# beltpack_v1_fixed.net
KiCad netlist of a schematic drawn in EAGLE
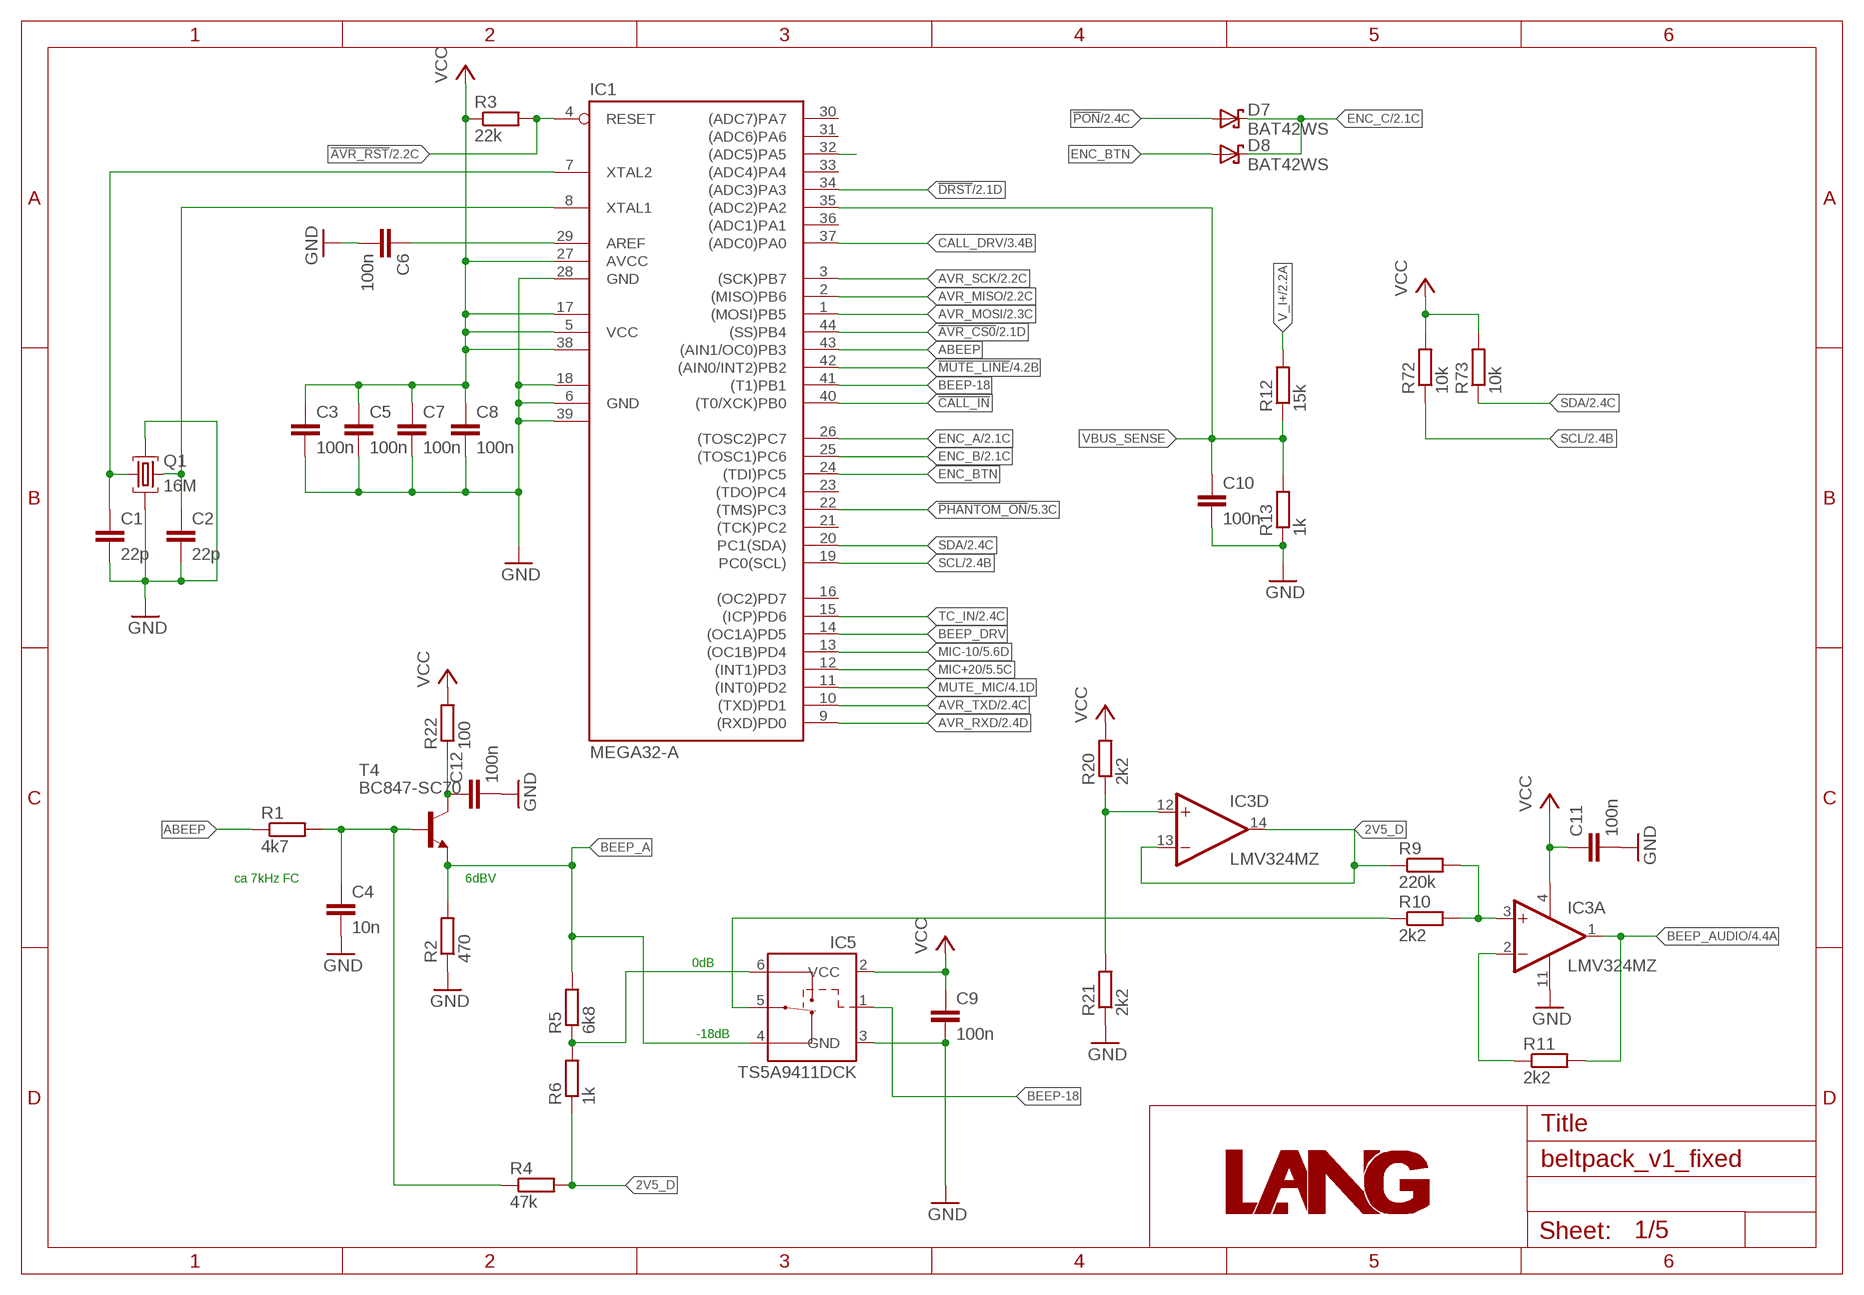
[diagram p0: schematic, sheet 1]
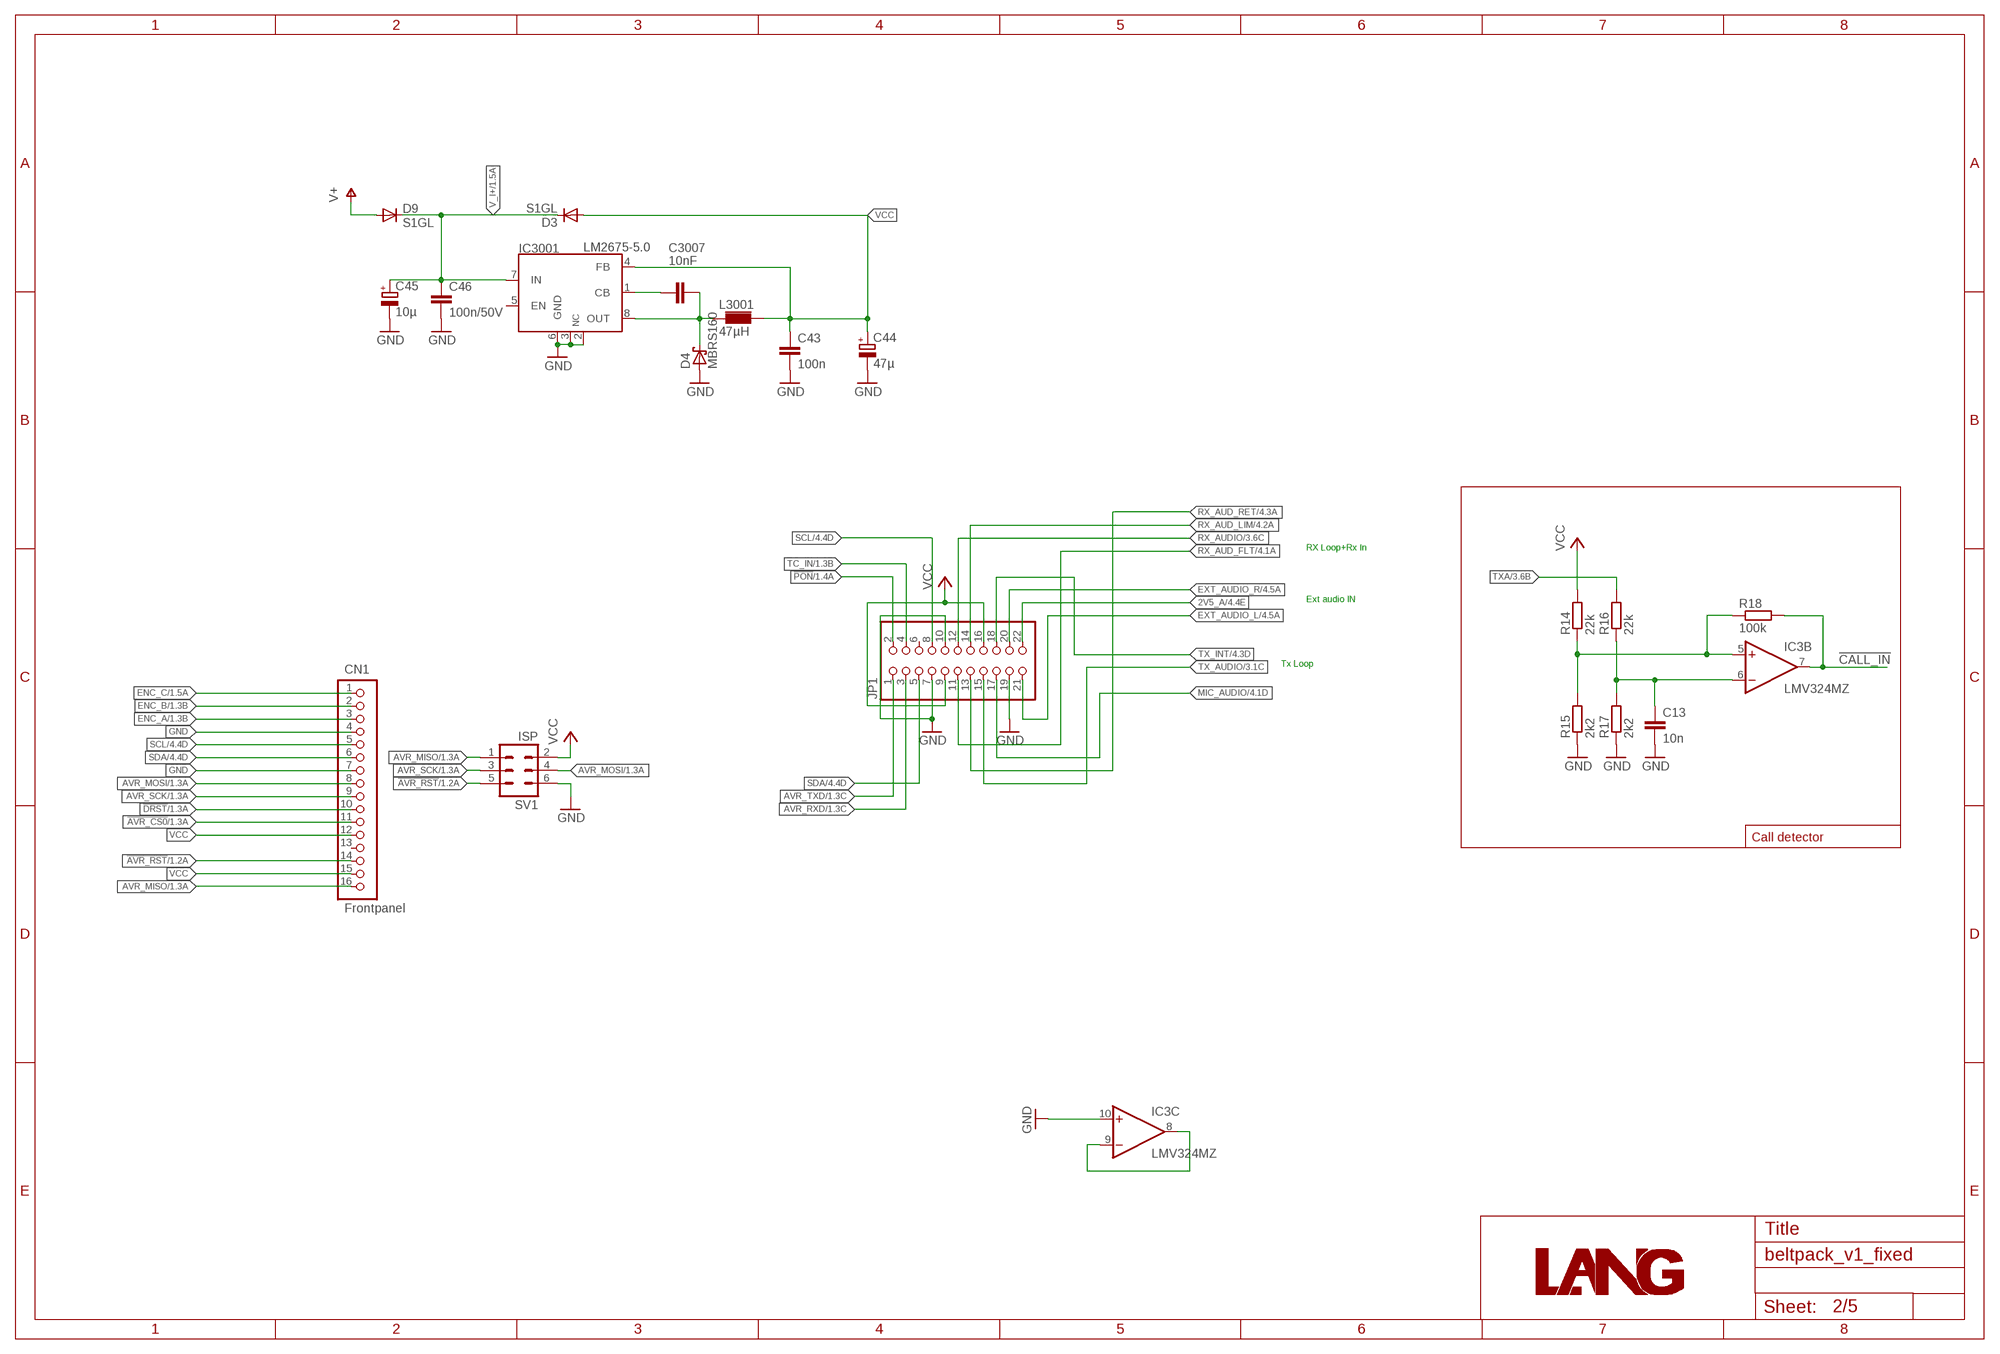
[diagram p1: schematic, sheet 2]
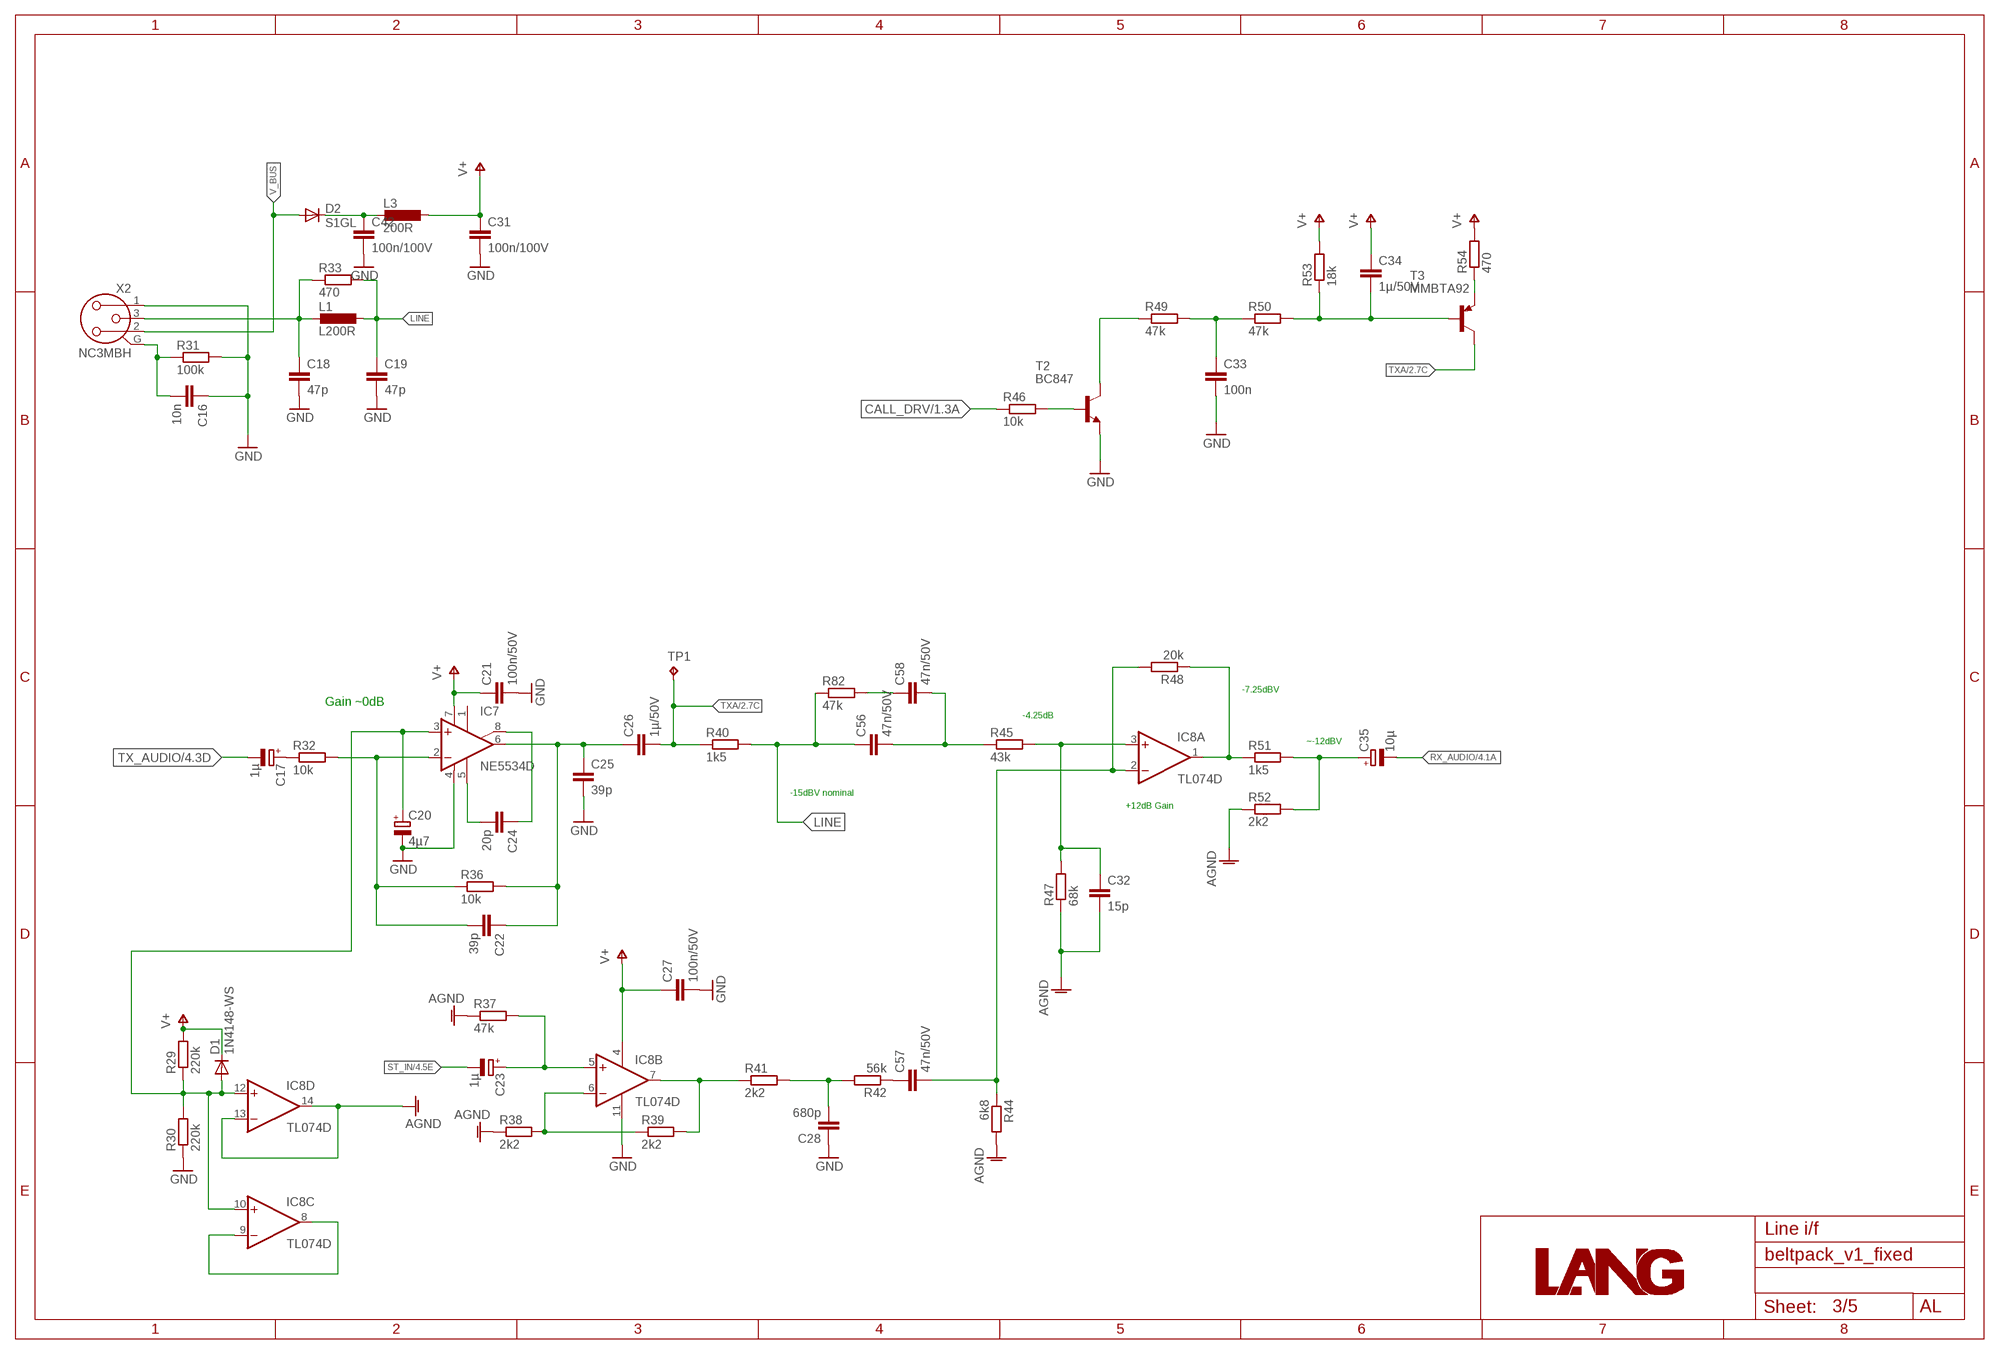
[diagram p2: schematic, sheet 3]
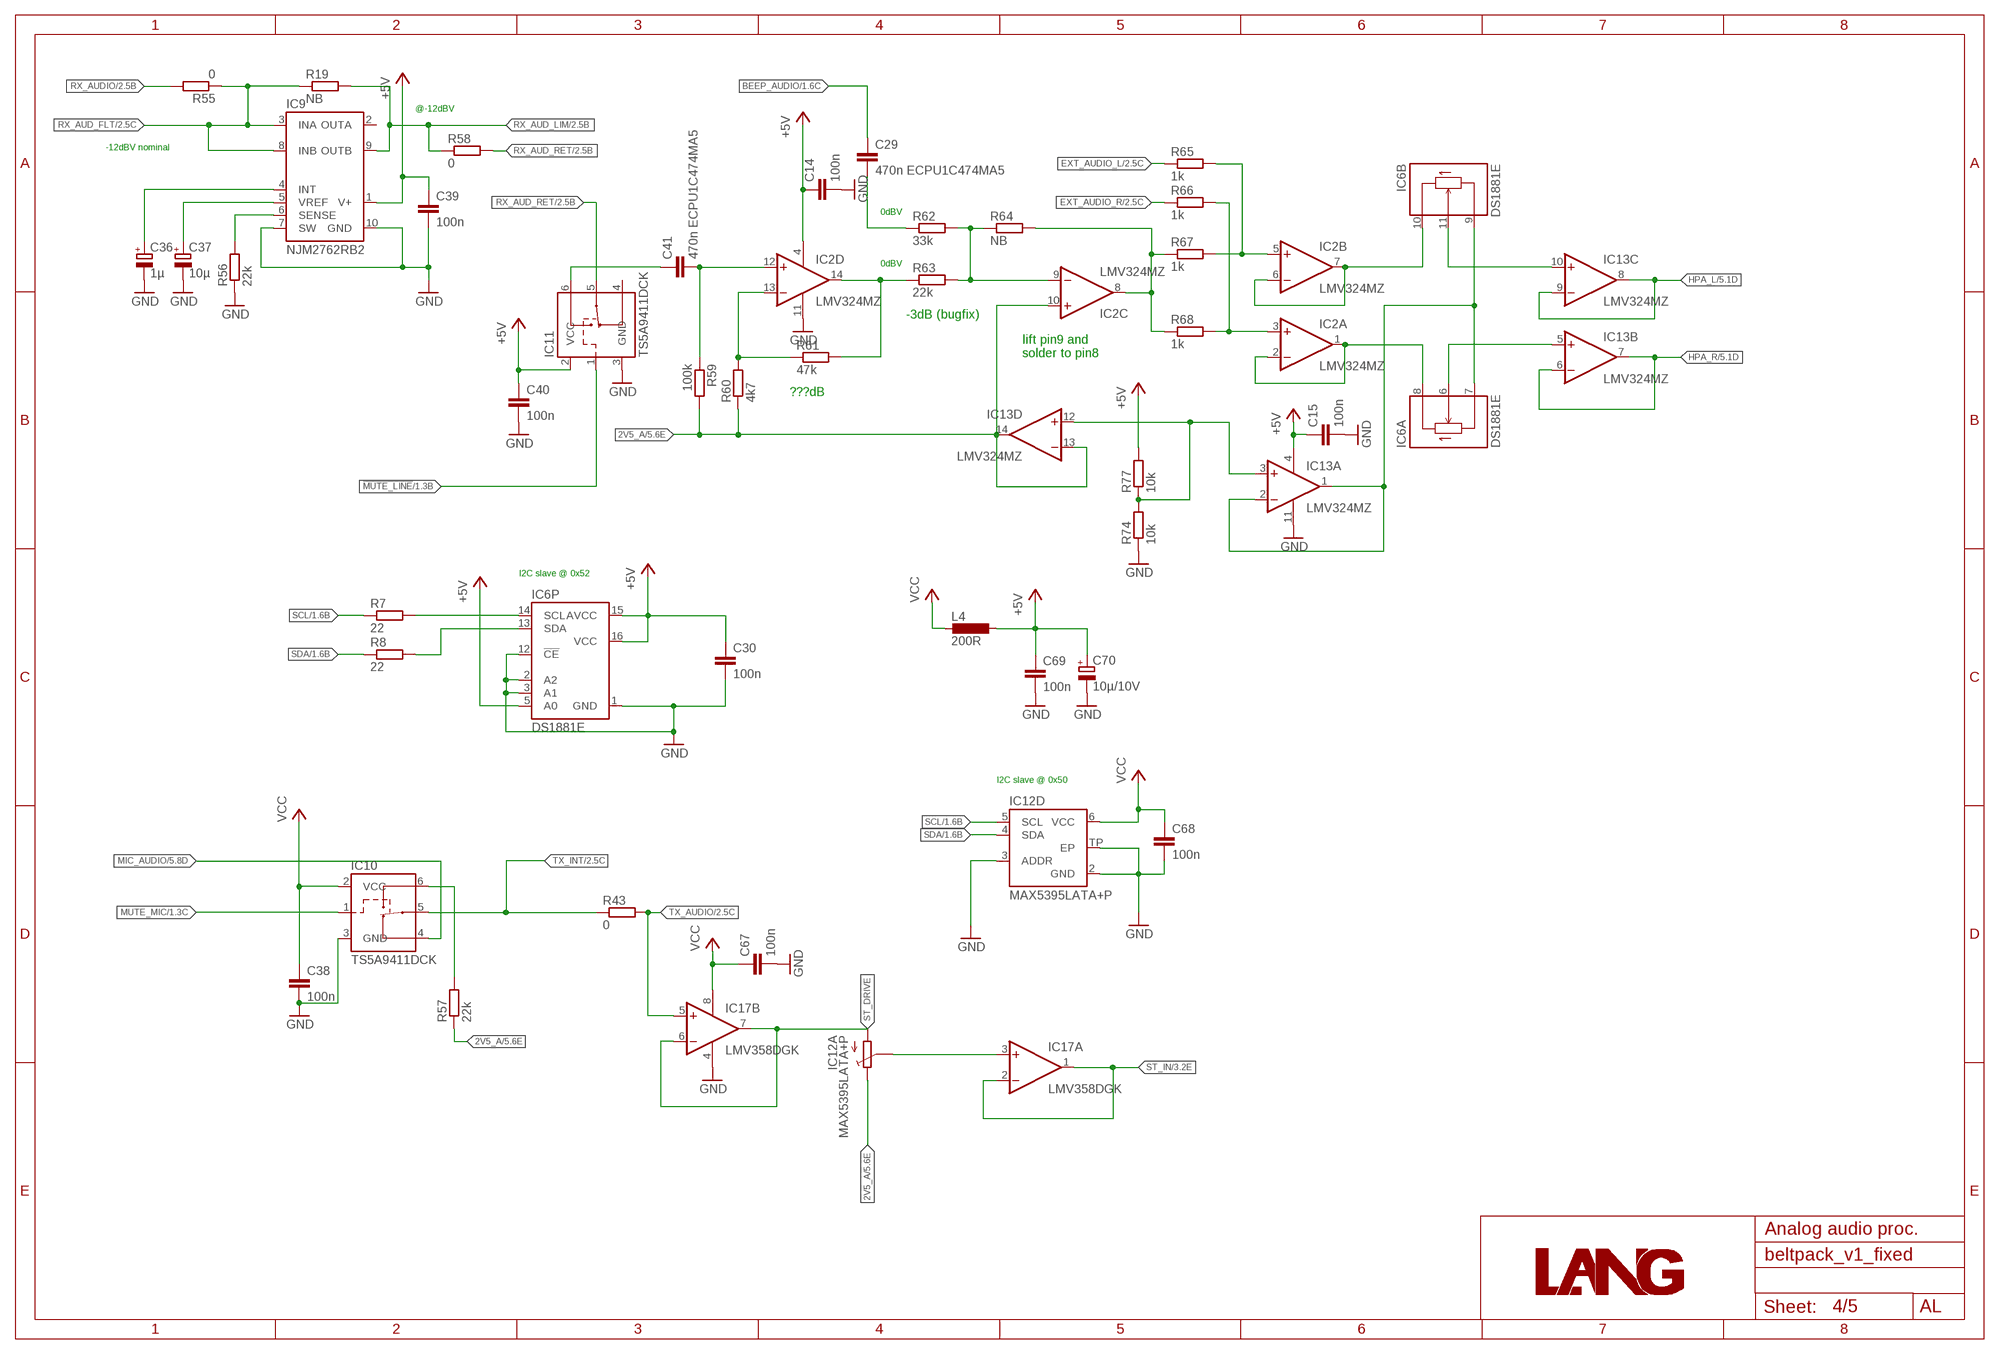
[diagram p3: schematic, sheet 4]
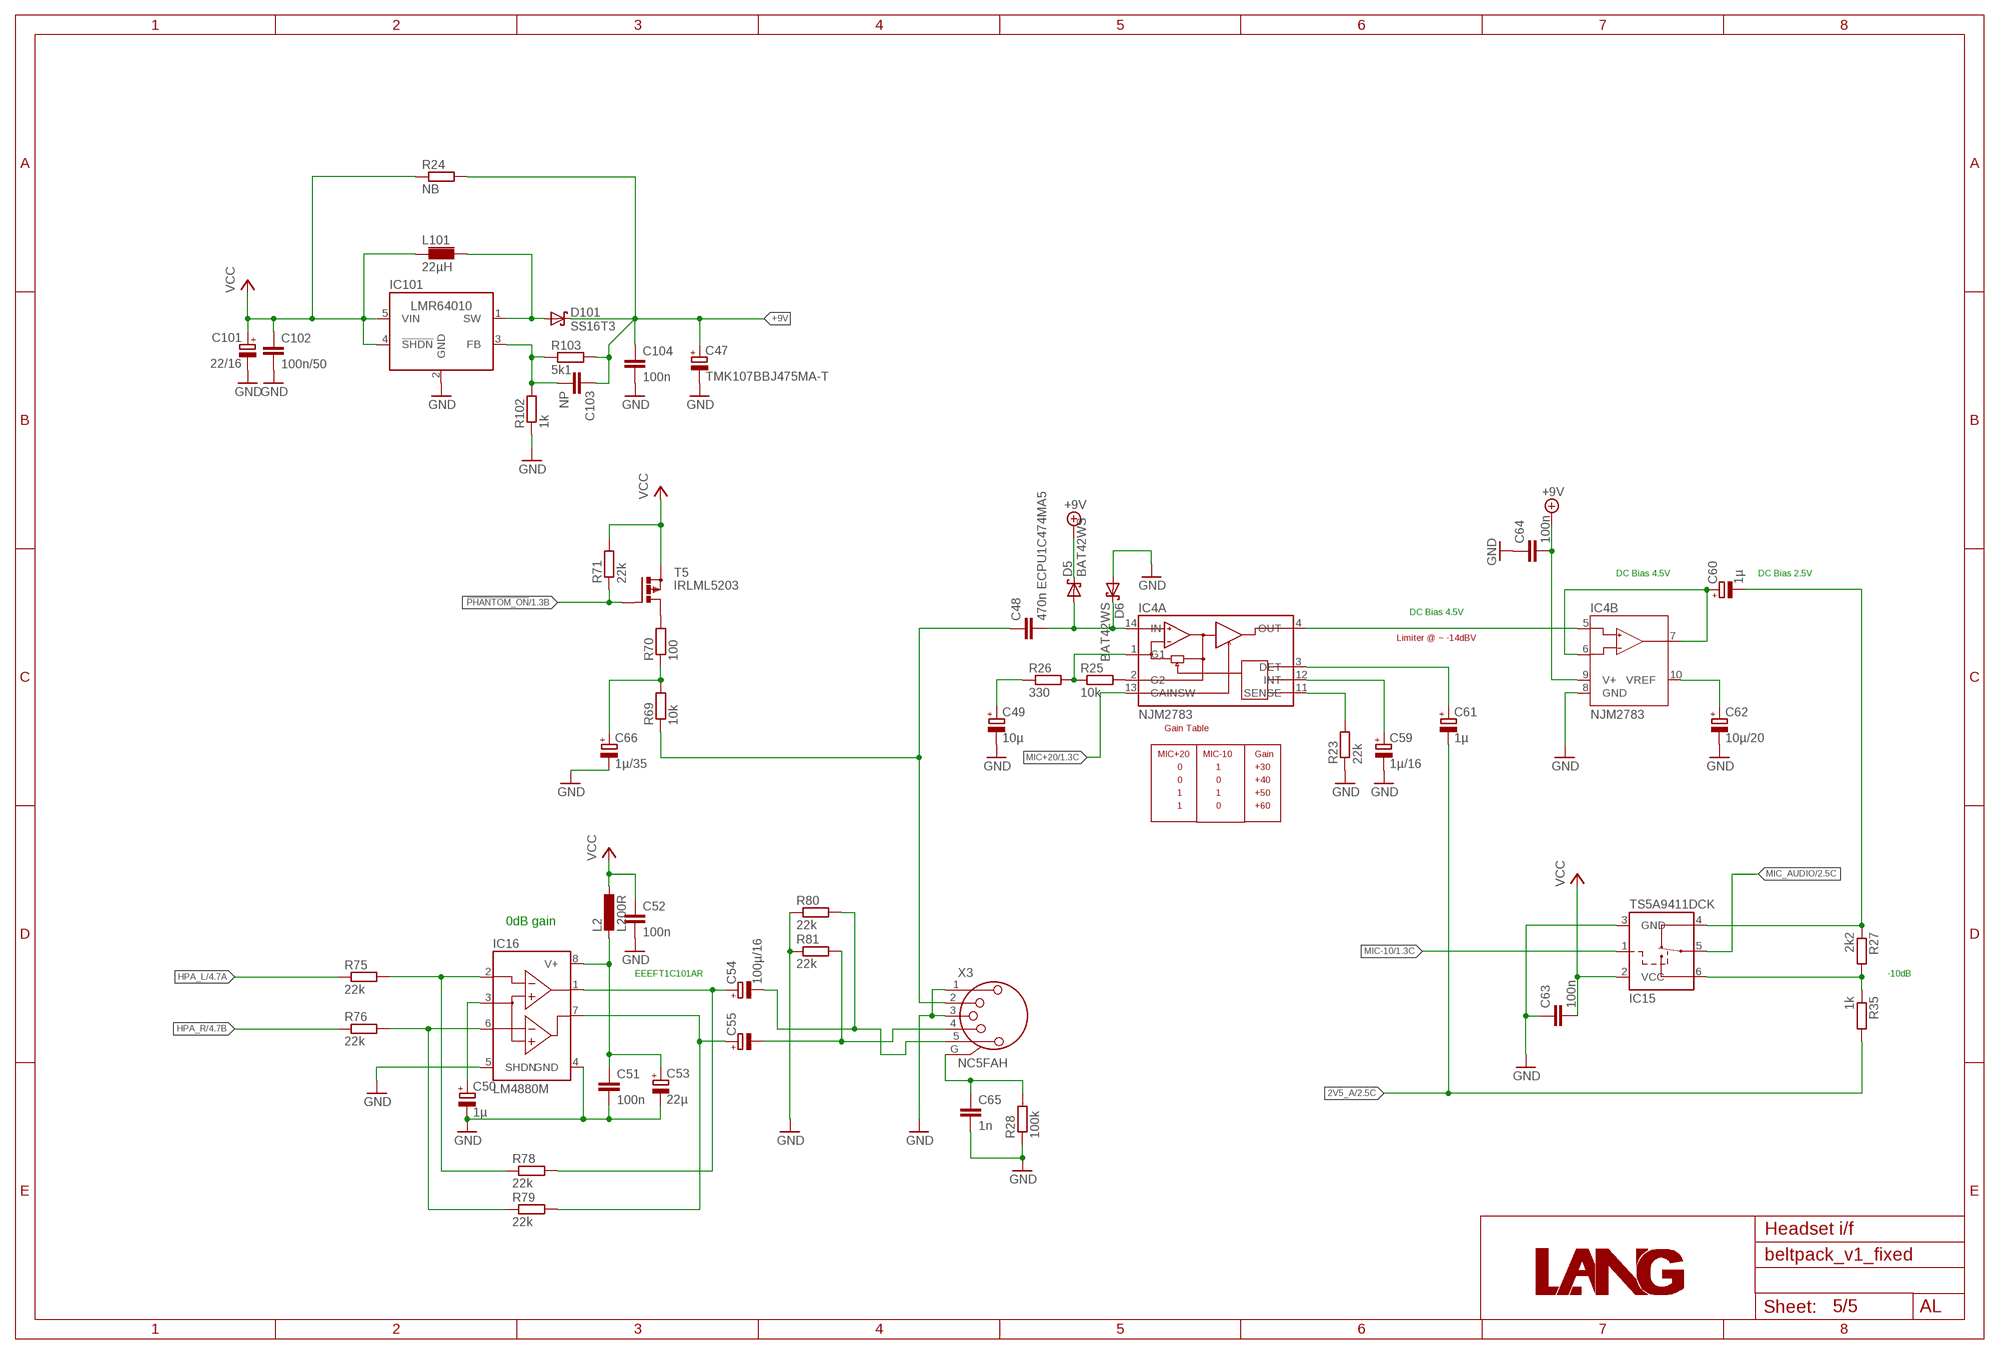
[diagram p4: schematic, sheet 5]

(export (version "E")
  (design (tool "Eeschema 10.0.6"))
  (components
    (comp (ref "C1")
      (value "22p")
      (footprint "eagle-import:C0603")
      (libsource (lib "eagle-import") (part "C-EUC0603"))
    )
    (comp (ref "C2")
      (value "22p")
      (footprint "eagle-import:C0603")
      (libsource (lib "eagle-import") (part "C-EUC0603"))
    )
    (comp (ref "C3")
      (value "100n")
      (footprint "eagle-import:C0603")
      (libsource (lib "eagle-import") (part "C-EUC0603"))
    )
    (comp (ref "C4")
      (value "10n")
      (footprint "eagle-import:C0603")
      (libsource (lib "eagle-import") (part "C-EUC0603"))
    )
    (comp (ref "C5")
      (value "100n")
      (footprint "eagle-import:C0603")
      (libsource (lib "eagle-import") (part "C-EUC0603"))
    )
    (comp (ref "C6")
      (value "100n")
      (footprint "eagle-import:C0603")
      (libsource (lib "eagle-import") (part "C-EUC0603"))
    )
    (comp (ref "C7")
      (value "100n")
      (footprint "eagle-import:C0603")
      (libsource (lib "eagle-import") (part "C-EUC0603"))
    )
    (comp (ref "C8")
      (value "100n")
      (footprint "eagle-import:C0603")
      (libsource (lib "eagle-import") (part "C-EUC0603"))
    )
    (comp (ref "C9")
      (value "100n")
      (footprint "eagle-import:C0603")
      (libsource (lib "eagle-import") (part "C-EUC0603"))
    )
    (comp (ref "C10")
      (value "100n")
      (footprint "eagle-import:C0603")
      (libsource (lib "eagle-import") (part "C-EUC0603"))
    )
    (comp (ref "C11")
      (value "100n")
      (footprint "eagle-import:C0603")
      (libsource (lib "eagle-import") (part "C-EUC0603"))
    )
    (comp (ref "C12")
      (value "100n")
      (footprint "eagle-import:C0603")
      (libsource (lib "eagle-import") (part "C-EUC0603"))
    )
    (comp (ref "D7")
      (value "BAT42WS")
      (footprint "eagle-import:SOD323R_INFINEON")
      (libsource (lib "eagle-import") (part "BAT4WS2"))
    )
    (comp (ref "D8")
      (value "BAT42WS")
      (footprint "eagle-import:SOD323R_INFINEON")
      (libsource (lib "eagle-import") (part "BAT4WS2"))
    )
    (comp (ref "IC1")
      (value "MEGA32-A")
      (footprint "eagle-import:TQFP44")
      (libsource (lib "eagle-import") (part "MEGA32-A"))
    )
    (comp (ref "IC3")
      (value "LMV324MZ")
      (footprint "eagle-import:TSSOP14")
      (libsource (lib "eagle-import") (part "LMV324?MZ"))
    )
    (comp (ref "IC5")
      (value "TS5A9411DCK")
      (footprint "eagle-import:SC70-6L")
      (libsource (lib "eagle-import") (part "TS5A9411DCK"))
    )
    (comp (ref "Q1")
      (value "16M")
      (footprint "eagle-import:MT")
      (libsource (lib "eagle-import") (part "CRYSTAL_SHIELDEDMT"))
    )
    (comp (ref "R1")
      (value "4k7")
      (footprint "eagle-import:R0603")
      (libsource (lib "eagle-import") (part "R-EU_R0603"))
    )
    (comp (ref "R2")
      (value "470")
      (footprint "eagle-import:R0603")
      (libsource (lib "eagle-import") (part "R-EU_R0603"))
    )
    (comp (ref "R3")
      (value "22k")
      (footprint "eagle-import:R0603")
      (libsource (lib "eagle-import") (part "R-EU_R0603"))
    )
    (comp (ref "R4")
      (value "47k")
      (footprint "eagle-import:R0603")
      (libsource (lib "eagle-import") (part "R-EU_R0603"))
    )
    (comp (ref "R5")
      (value "6k8")
      (footprint "eagle-import:R0603")
      (libsource (lib "eagle-import") (part "R-EU_R0603"))
    )
    (comp (ref "R6")
      (value "1k")
      (footprint "eagle-import:R0603")
      (libsource (lib "eagle-import") (part "R-EU_R0603"))
    )
    (comp (ref "R9")
      (value "220k")
      (footprint "eagle-import:R0603")
      (libsource (lib "eagle-import") (part "R-EU_R0603"))
    )
    (comp (ref "R10")
      (value "2k2")
      (footprint "eagle-import:R0603")
      (libsource (lib "eagle-import") (part "R-EU_R0603"))
    )
    (comp (ref "R11")
      (value "2k2")
      (footprint "eagle-import:R0603")
      (libsource (lib "eagle-import") (part "R-EU_R0603"))
    )
    (comp (ref "R12")
      (value "15k")
      (footprint "eagle-import:R0603")
      (libsource (lib "eagle-import") (part "R-EU_R0603"))
    )
    (comp (ref "R13")
      (value "1k")
      (footprint "eagle-import:R0603")
      (libsource (lib "eagle-import") (part "R-EU_R0603"))
    )
    (comp (ref "R20")
      (value "2k2")
      (footprint "eagle-import:R0603")
      (libsource (lib "eagle-import") (part "R-EU_R0603"))
    )
    (comp (ref "R21")
      (value "2k2")
      (footprint "eagle-import:R0603")
      (libsource (lib "eagle-import") (part "R-EU_R0603"))
    )
    (comp (ref "R22")
      (value "100")
      (footprint "eagle-import:R0603")
      (libsource (lib "eagle-import") (part "R-EU_R0603"))
    )
    (comp (ref "R72")
      (value "10k")
      (footprint "eagle-import:R0603")
      (libsource (lib "eagle-import") (part "R-EU_R0603"))
    )
    (comp (ref "R73")
      (value "10k")
      (footprint "eagle-import:R0603")
      (libsource (lib "eagle-import") (part "R-EU_R0603"))
    )
    (comp (ref "T4")
      (value "BC847-SC70")
      (footprint "eagle-import:SC70")
      (libsource (lib "eagle-import") (part "BC847-SC70"))
    )
    (comp (ref "C13")
      (value "10n")
      (footprint "eagle-import:C0603")
      (libsource (lib "eagle-import") (part "C-EUC0603"))
    )
    (comp (ref "C43")
      (value "100n")
      (footprint "eagle-import:C0603")
      (libsource (lib "eagle-import") (part "C-EUC0603"))
    )
    (comp (ref "C44")
      (value "47µ")
      (footprint "eagle-import:PANASONIC_B")
      (libsource (lib "eagle-import") (part "CPOL-EUB"))
    )
    (comp (ref "C45")
      (value "10µ")
      (footprint "eagle-import:PANASONIC_C")
      (libsource (lib "eagle-import") (part "CPOL-EUC"))
    )
    (comp (ref "C46")
      (value "100n/50V")
      (footprint "eagle-import:C0805")
      (libsource (lib "eagle-import") (part "C-EUC0805"))
    )
    (comp (ref "C3007")
      (value "10nF")
      (footprint "eagle-import:C0805")
      (libsource (lib "eagle-import") (part "C-EUC0805"))
    )
    (comp (ref "CN1")
      (value "Frontpanel")
      (footprint "eagle-import:MOLEX-505278-1633")
      (libsource (lib "eagle-import") (part "MOLEX-505278-1633"))
    )
    (comp (ref "D3")
      (value "S1GL")
      (footprint "eagle-import:DO219AB")
      (libsource (lib "eagle-import") (part "DIODE-DO219AB"))
    )
    (comp (ref "D4")
      (value "MBRS160")
      (footprint "eagle-import:SMB")
      (libsource (lib "eagle-import") (part "SCHOTTKY-DIODESMD"))
    )
    (comp (ref "D9")
      (value "S1GL")
      (footprint "eagle-import:DO219AB")
      (libsource (lib "eagle-import") (part "DIODE-DO219AB"))
    )
    (comp (ref "IC3001")
      (value "LM2675-5.0")
      (footprint "eagle-import:SO-08")
      (libsource (lib "eagle-import") (part "LM2676_SOIC"))
    )
    (comp (ref "JP1")
      (value "PINHD-2X11")
      (footprint "eagle-import:2X11")
      (libsource (lib "eagle-import") (part "PINHD-2X11"))
    )
    (comp (ref "L3001")
      (value "47µH")
      (footprint "eagle-import:PISM")
      (libsource (lib "eagle-import") (part "L-PISM"))
    )
    (comp (ref "R14")
      (value "22k")
      (footprint "eagle-import:R0603")
      (libsource (lib "eagle-import") (part "R-EU_R0603"))
    )
    (comp (ref "R15")
      (value "2k2")
      (footprint "eagle-import:R0603")
      (libsource (lib "eagle-import") (part "R-EU_R0603"))
    )
    (comp (ref "R16")
      (value "22k")
      (footprint "eagle-import:R0603")
      (libsource (lib "eagle-import") (part "R-EU_R0603"))
    )
    (comp (ref "R17")
      (value "2k2")
      (footprint "eagle-import:R0603")
      (libsource (lib "eagle-import") (part "R-EU_R0603"))
    )
    (comp (ref "R18")
      (value "100k")
      (footprint "eagle-import:R0603")
      (libsource (lib "eagle-import") (part "R-EU_R0603"))
    )
    (comp (ref "SV1")
      (value "ISP")
      (footprint "eagle-import:ML6")
      (libsource (lib "eagle-import") (part "ML6"))
    )
    (comp (ref "C14")
      (value "100n")
      (footprint "eagle-import:C0603")
      (libsource (lib "eagle-import") (part "C-EUC0603"))
    )
    (comp (ref "C15")
      (value "100n")
      (footprint "eagle-import:C0603")
      (libsource (lib "eagle-import") (part "C-EUC0603"))
    )
    (comp (ref "C29")
      (value "470n ECPU1C474MA5")
      (footprint "eagle-import:C_PANASONIC_H3")
      (libsource (lib "eagle-import") (part "C-EUPAN_H3"))
    )
    (comp (ref "C30")
      (value "100n")
      (footprint "eagle-import:C0603")
      (libsource (lib "eagle-import") (part "C-EUC0603"))
    )
    (comp (ref "C36")
      (value "1µ")
      (footprint "eagle-import:PANASONIC_B")
      (libsource (lib "eagle-import") (part "CPOL-EUB"))
    )
    (comp (ref "C37")
      (value "10µ")
      (footprint "eagle-import:PANASONIC_B")
      (libsource (lib "eagle-import") (part "CPOL-EUB"))
    )
    (comp (ref "C38")
      (value "100n")
      (footprint "eagle-import:C0402")
      (libsource (lib "eagle-import") (part "C-EUC0402"))
    )
    (comp (ref "C39")
      (value "100n")
      (footprint "eagle-import:C0603")
      (libsource (lib "eagle-import") (part "C-EUC0603"))
    )
    (comp (ref "C40")
      (value "100n")
      (footprint "eagle-import:C0603")
      (libsource (lib "eagle-import") (part "C-EUC0603"))
    )
    (comp (ref "C41")
      (value "470n ECPU1C474MA5")
      (footprint "eagle-import:C_PANASONIC_H3")
      (libsource (lib "eagle-import") (part "C-EUPAN_H3"))
    )
    (comp (ref "C67")
      (value "100n")
      (footprint "eagle-import:C0603")
      (libsource (lib "eagle-import") (part "C-EUC0603"))
    )
    (comp (ref "C68")
      (value "100n")
      (footprint "eagle-import:C0603")
      (libsource (lib "eagle-import") (part "C-EUC0603"))
    )
    (comp (ref "C69")
      (value "100n")
      (footprint "eagle-import:C0603")
      (libsource (lib "eagle-import") (part "C-EUC0603"))
    )
    (comp (ref "C70")
      (value "10µ/10V")
      (footprint "eagle-import:A_3216-18R")
      (libsource (lib "eagle-import") (part "CPOL-EUA/3216-18R"))
    )
    (comp (ref "IC2")
      (value "LMV324MZ")
      (footprint "eagle-import:TSSOP14")
      (libsource (lib "eagle-import") (part "LMV324?MZ"))
    )
    (comp (ref "IC6")
      (value "DS1881E")
      (footprint "eagle-import:TSSOP16")
      (libsource (lib "eagle-import") (part "DS1881E"))
    )
    (comp (ref "IC9")
      (value "NJM2762RB2")
      (footprint "eagle-import:MSOP10")
      (libsource (lib "eagle-import") (part "NJM2762RB2"))
    )
    (comp (ref "IC10")
      (value "TS5A9411DCK")
      (footprint "eagle-import:SC70-6L")
      (libsource (lib "eagle-import") (part "TS5A9411DCK"))
    )
    (comp (ref "IC11")
      (value "TS5A9411DCK")
      (footprint "eagle-import:SC70-6L")
      (libsource (lib "eagle-import") (part "TS5A9411DCK"))
    )
    (comp (ref "IC12")
      (value "MAX5395LATA+P")
      (footprint "eagle-import:8TDFN-EP")
      (libsource (lib "eagle-import") (part "MAX5395ATA+PL"))
    )
    (comp (ref "IC13")
      (value "LMV324MZ")
      (footprint "eagle-import:TSSOP14")
      (libsource (lib "eagle-import") (part "LMV324?MZ"))
    )
    (comp (ref "IC17")
      (value "LMV358DGK")
      (footprint "eagle-import:VSOP8")
      (libsource (lib "eagle-import") (part "LMV358?DGK"))
    )
    (comp (ref "L4")
      (value "200R")
      (footprint "eagle-import:R0805")
      (libsource (lib "eagle-import") (part "L-EU_L0805"))
    )
    (comp (ref "R7")
      (value "22")
      (footprint "eagle-import:R0402")
      (libsource (lib "eagle-import") (part "R-EU_R0402"))
    )
    (comp (ref "R8")
      (value "22")
      (footprint "eagle-import:R0402")
      (libsource (lib "eagle-import") (part "R-EU_R0402"))
    )
    (comp (ref "R19")
      (value "NB")
      (footprint "eagle-import:R0603")
      (libsource (lib "eagle-import") (part "R-EU_R0603"))
    )
    (comp (ref "R43")
      (value "0")
      (footprint "eagle-import:R0603")
      (libsource (lib "eagle-import") (part "R-EU_R0603"))
    )
    (comp (ref "R55")
      (value "0")
      (footprint "eagle-import:R0603")
      (libsource (lib "eagle-import") (part "R-EU_R0603"))
    )
    (comp (ref "R56")
      (value "22k")
      (footprint "eagle-import:R0603")
      (libsource (lib "eagle-import") (part "R-EU_R0603"))
    )
    (comp (ref "R57")
      (value "22k")
      (footprint "eagle-import:R0603")
      (libsource (lib "eagle-import") (part "R-EU_R0603"))
    )
    (comp (ref "R58")
      (value "0")
      (footprint "eagle-import:R0603")
      (libsource (lib "eagle-import") (part "R-EU_R0603"))
    )
    (comp (ref "R59")
      (value "100k")
      (footprint "eagle-import:R0603")
      (libsource (lib "eagle-import") (part "R-EU_R0603"))
    )
    (comp (ref "R60")
      (value "4k7")
      (footprint "eagle-import:R0603")
      (libsource (lib "eagle-import") (part "R-EU_R0603"))
    )
    (comp (ref "R61")
      (value "47k")
      (footprint "eagle-import:R0603")
      (libsource (lib "eagle-import") (part "R-EU_R0603"))
    )
    (comp (ref "R62")
      (value "33k")
      (footprint "eagle-import:R0603")
      (libsource (lib "eagle-import") (part "R-EU_R0603"))
    )
    (comp (ref "R63")
      (value "22k")
      (footprint "eagle-import:R0603")
      (libsource (lib "eagle-import") (part "R-EU_R0603"))
    )
    (comp (ref "R64")
      (value "NB")
      (footprint "eagle-import:R0603")
      (libsource (lib "eagle-import") (part "R-EU_R0603"))
    )
    (comp (ref "R65")
      (value "1k")
      (footprint "eagle-import:R0603")
      (libsource (lib "eagle-import") (part "R-EU_R0603"))
    )
    (comp (ref "R66")
      (value "1k")
      (footprint "eagle-import:R0603")
      (libsource (lib "eagle-import") (part "R-EU_R0603"))
    )
    (comp (ref "R67")
      (value "1k")
      (footprint "eagle-import:R0603")
      (libsource (lib "eagle-import") (part "R-EU_R0603"))
    )
    (comp (ref "R68")
      (value "1k")
      (footprint "eagle-import:R0603")
      (libsource (lib "eagle-import") (part "R-EU_R0603"))
    )
    (comp (ref "R74")
      (value "10k")
      (footprint "eagle-import:R0603")
      (libsource (lib "eagle-import") (part "R-EU_R0603"))
    )
    (comp (ref "R77")
      (value "10k")
      (footprint "eagle-import:R0603")
      (libsource (lib "eagle-import") (part "R-EU_R0603"))
    )
    (comp (ref "C47")
      (value "TMK107BBJ475MA-T")
      (footprint "eagle-import:PANASONIC_B")
      (libsource (lib "eagle-import") (part "CPOL-EUB"))
    )
    (comp (ref "C48")
      (value "470n ECPU1C474MA5")
      (footprint "eagle-import:C_PANASONIC_H3")
      (libsource (lib "eagle-import") (part "C-EUPAN_H3"))
    )
    (comp (ref "C49")
      (value "10µ")
      (footprint "eagle-import:PANASONIC_B")
      (libsource (lib "eagle-import") (part "CPOL-EUB"))
    )
    (comp (ref "C50")
      (value "1µ")
      (footprint "eagle-import:PANASONIC_B")
      (libsource (lib "eagle-import") (part "CPOL-EUB"))
    )
    (comp (ref "C51")
      (value "100n")
      (footprint "eagle-import:C0603")
      (libsource (lib "eagle-import") (part "C-EUC0603"))
    )
    (comp (ref "C52")
      (value "100n")
      (footprint "eagle-import:C0603")
      (libsource (lib "eagle-import") (part "C-EUC0603"))
    )
    (comp (ref "C53")
      (value "22µ")
      (footprint "eagle-import:PANASONIC_C")
      (libsource (lib "eagle-import") (part "CPOL-EUC"))
    )
    (comp (ref "C54")
      (value "100µ/16")
      (footprint "eagle-import:PANASONIC_C")
      (libsource (lib "eagle-import") (part "CPOL-EUC"))
    )
    (comp (ref "C55")
      (value "100µ/16")
      (footprint "eagle-import:PANASONIC_C")
      (libsource (lib "eagle-import") (part "CPOL-EUC"))
    )
    (comp (ref "C59")
      (value "1µ/16")
      (footprint "eagle-import:A_3216-18R")
      (libsource (lib "eagle-import") (part "CPOL-EUA/3216-18R"))
    )
    (comp (ref "C60")
      (value "1µ")
      (footprint "eagle-import:PANASONIC_B")
      (libsource (lib "eagle-import") (part "CPOL-EUB"))
    )
    (comp (ref "C61")
      (value "1µ")
      (footprint "eagle-import:PANASONIC_B")
      (libsource (lib "eagle-import") (part "CPOL-EUB"))
    )
    (comp (ref "C62")
      (value "10µ/20")
      (footprint "eagle-import:B_3528-21R")
      (libsource (lib "eagle-import") (part "CPOL-EUB/3528-21R"))
    )
    (comp (ref "C63")
      (value "100n")
      (footprint "eagle-import:C0402")
      (libsource (lib "eagle-import") (part "C-EUC0402"))
    )
    (comp (ref "C64")
      (value "100n")
      (footprint "eagle-import:C0603")
      (libsource (lib "eagle-import") (part "C-EUC0603"))
    )
    (comp (ref "C65")
      (value "1n")
      (footprint "eagle-import:C0603")
      (libsource (lib "eagle-import") (part "C-EUC0603"))
    )
    (comp (ref "C66")
      (value "1µ/35")
      (footprint "eagle-import:B_3528-21R")
      (libsource (lib "eagle-import") (part "CPOL-EUB/3528-21R"))
    )
    (comp (ref "C101")
      (value "22/16")
      (footprint "eagle-import:B_3528-21R")
      (libsource (lib "eagle-import") (part "CPOL-EUB/3528-21R"))
    )
    (comp (ref "C102")
      (value "100n/50")
      (footprint "eagle-import:C0805")
      (libsource (lib "eagle-import") (part "C-EUC0805"))
    )
    (comp (ref "C103")
      (value "NP")
      (footprint "eagle-import:C0603")
      (libsource (lib "eagle-import") (part "C-EUC0603"))
    )
    (comp (ref "C104")
      (value "100n")
      (footprint "eagle-import:C0603")
      (libsource (lib "eagle-import") (part "C-EUC0603"))
    )
    (comp (ref "D5")
      (value "BAT42WS")
      (footprint "eagle-import:SOD323R_INFINEON")
      (libsource (lib "eagle-import") (part "BAT4WS2"))
    )
    (comp (ref "D6")
      (value "BAT42WS")
      (footprint "eagle-import:SOD323R_INFINEON")
      (libsource (lib "eagle-import") (part "BAT4WS2"))
    )
    (comp (ref "D101")
      (value "SS16T3")
      (footprint "eagle-import:SMA")
      (libsource (lib "eagle-import") (part "SS16T3"))
    )
    (comp (ref "IC4")
      (value "NJM2783")
      (footprint "eagle-import:TSSOP14")
      (libsource (lib "eagle-import") (part "NJM2783"))
    )
    (comp (ref "IC15")
      (value "TS5A9411DCK")
      (footprint "eagle-import:SC70-6L")
      (libsource (lib "eagle-import") (part "TS5A9411DCK"))
    )
    (comp (ref "IC16")
      (value "LM4880M")
      (footprint "eagle-import:SOIC8")
      (libsource (lib "eagle-import") (part "LM4880M"))
    )
    (comp (ref "IC101")
      (value "LMR64010")
      (footprint "eagle-import:SOT23-5")
      (libsource (lib "eagle-import") (part "LMR64010"))
    )
    (comp (ref "L2")
      (value "L200R")
      (footprint "eagle-import:R0805")
      (libsource (lib "eagle-import") (part "L-EU_L0805"))
    )
    (comp (ref "L101")
      (value "22µH")
      (footprint "eagle-import:PISG")
      (libsource (lib "eagle-import") (part "L-PISG"))
    )
    (comp (ref "R23")
      (value "22k")
      (footprint "eagle-import:R0603")
      (libsource (lib "eagle-import") (part "R-EU_R0603"))
    )
    (comp (ref "R24")
      (value "NB")
      (footprint "eagle-import:R0603")
      (libsource (lib "eagle-import") (part "R-EU_R0603"))
    )
    (comp (ref "R25")
      (value "10k")
      (footprint "eagle-import:R0603")
      (libsource (lib "eagle-import") (part "R-EU_R0603"))
    )
    (comp (ref "R26")
      (value "330")
      (footprint "eagle-import:R0603")
      (libsource (lib "eagle-import") (part "R-EU_R0603"))
    )
    (comp (ref "R27")
      (value "2k2")
      (footprint "eagle-import:R0603")
      (libsource (lib "eagle-import") (part "R-EU_R0603"))
    )
    (comp (ref "R28")
      (value "100k")
      (footprint "eagle-import:R0603")
      (libsource (lib "eagle-import") (part "R-EU_R0603"))
    )
    (comp (ref "R35")
      (value "1k")
      (footprint "eagle-import:R0603")
      (libsource (lib "eagle-import") (part "R-EU_R0603"))
    )
    (comp (ref "R69")
      (value "10k")
      (footprint "eagle-import:R0603")
      (libsource (lib "eagle-import") (part "R-EU_R0603"))
    )
    (comp (ref "R70")
      (value "100")
      (footprint "eagle-import:R0603")
      (libsource (lib "eagle-import") (part "R-EU_R0603"))
    )
    (comp (ref "R71")
      (value "22k")
      (footprint "eagle-import:R0603")
      (libsource (lib "eagle-import") (part "R-EU_R0603"))
    )
    (comp (ref "R75")
      (value "22k")
      (footprint "eagle-import:R0603")
      (libsource (lib "eagle-import") (part "R-EU_R0603"))
    )
    (comp (ref "R76")
      (value "22k")
      (footprint "eagle-import:R0603")
      (libsource (lib "eagle-import") (part "R-EU_R0603"))
    )
    (comp (ref "R78")
      (value "22k")
      (footprint "eagle-import:R0603")
      (libsource (lib "eagle-import") (part "R-EU_R0603"))
    )
    (comp (ref "R79")
      (value "22k")
      (footprint "eagle-import:R0603")
      (libsource (lib "eagle-import") (part "R-EU_R0603"))
    )
    (comp (ref "R80")
      (value "22k")
      (footprint "eagle-import:R0603")
      (libsource (lib "eagle-import") (part "R-EU_R0603"))
    )
    (comp (ref "R81")
      (value "22k")
      (footprint "eagle-import:R0603")
      (libsource (lib "eagle-import") (part "R-EU_R0603"))
    )
    (comp (ref "R102")
      (value "1k")
      (footprint "eagle-import:R0603")
      (libsource (lib "eagle-import") (part "R-EU_R0603"))
    )
    (comp (ref "R103")
      (value "5k1")
      (footprint "eagle-import:R0603")
      (libsource (lib "eagle-import") (part "R-EU_R0603"))
    )
    (comp (ref "T5")
      (value "IRLML5203")
      (footprint "eagle-import:SOT23")
      (libsource (lib "eagle-import") (part "IRLML5203"))
    )
    (comp (ref "X3")
      (value "NC5FAH")
      (footprint "eagle-import:NC5FAH")
      (libsource (lib "eagle-import") (part "NC5FAH"))
    )
    (comp (ref "C16")
      (value "10n")
      (footprint "eagle-import:C0805")
      (libsource (lib "eagle-import") (part "C-EUC0805"))
    )
    (comp (ref "C17")
      (value "1µ")
      (footprint "eagle-import:PANASONIC_B")
      (libsource (lib "eagle-import") (part "CPOL-EUB"))
    )
    (comp (ref "C18")
      (value "47p")
      (footprint "eagle-import:C0603")
      (libsource (lib "eagle-import") (part "C-EUC0603"))
    )
    (comp (ref "C19")
      (value "47p")
      (footprint "eagle-import:C0603")
      (libsource (lib "eagle-import") (part "C-EUC0603"))
    )
    (comp (ref "C20")
      (value "4µ7")
      (footprint "eagle-import:PANASONIC_B")
      (libsource (lib "eagle-import") (part "CPOL-EUB"))
    )
    (comp (ref "C21")
      (value "100n/50V")
      (footprint "eagle-import:C0805")
      (libsource (lib "eagle-import") (part "C-EUC0805"))
    )
    (comp (ref "C22")
      (value "39p")
      (footprint "eagle-import:C0603")
      (libsource (lib "eagle-import") (part "C-EUC0603"))
    )
    (comp (ref "C23")
      (value "1µ")
      (footprint "eagle-import:PANASONIC_B")
      (libsource (lib "eagle-import") (part "CPOL-EUB"))
    )
    (comp (ref "C24")
      (value "20p")
      (footprint "eagle-import:C0603")
      (libsource (lib "eagle-import") (part "C-EUC0603"))
    )
    (comp (ref "C25")
      (value "39p")
      (footprint "eagle-import:C0603")
      (libsource (lib "eagle-import") (part "C-EUC0603"))
    )
    (comp (ref "C26")
      (value "1µ/50V")
      (footprint "eagle-import:C1206")
      (libsource (lib "eagle-import") (part "C-EUC1206"))
    )
    (comp (ref "C27")
      (value "100n/50V")
      (footprint "eagle-import:C0805")
      (libsource (lib "eagle-import") (part "C-EUC0805"))
    )
    (comp (ref "C28")
      (value "680p")
      (footprint "eagle-import:C0603")
      (libsource (lib "eagle-import") (part "C-EUC0603"))
    )
    (comp (ref "C31")
      (value "100n/100V")
      (footprint "eagle-import:C1206")
      (libsource (lib "eagle-import") (part "C-EUC1206"))
    )
    (comp (ref "C32")
      (value "15p")
      (footprint "eagle-import:C0603")
      (libsource (lib "eagle-import") (part "C-EUC0603"))
    )
    (comp (ref "C33")
      (value "100n")
      (footprint "eagle-import:C0603")
      (libsource (lib "eagle-import") (part "C-EUC0603"))
    )
    (comp (ref "C34")
      (value "1µ/50V")
      (footprint "eagle-import:C1206")
      (libsource (lib "eagle-import") (part "C-EUC1206"))
    )
    (comp (ref "C35")
      (value "10µ")
      (footprint "eagle-import:PANASONIC_B")
      (libsource (lib "eagle-import") (part "CPOL-EUB"))
    )
    (comp (ref "C42")
      (value "100n/100V")
      (footprint "eagle-import:C1206")
      (libsource (lib "eagle-import") (part "C-EUC1206"))
    )
    (comp (ref "C56")
      (value "47n/50V")
      (footprint "eagle-import:C_PAN_ECHU_E1")
      (libsource (lib "eagle-import") (part "C-EUPAN_E1"))
    )
    (comp (ref "C57")
      (value "47n/50V")
      (footprint "eagle-import:C_PAN_ECHU_E1")
      (libsource (lib "eagle-import") (part "C-EUPAN_E1"))
    )
    (comp (ref "C58")
      (value "47n/50V")
      (footprint "eagle-import:C_PAN_ECHU_E1")
      (libsource (lib "eagle-import") (part "C-EUPAN_E1"))
    )
    (comp (ref "D1")
      (value "1N4148-WS")
      (footprint "eagle-import:SOD323")
      (libsource (lib "eagle-import") (part "1N4148-WS"))
    )
    (comp (ref "D2")
      (value "S1GL")
      (footprint "eagle-import:DO219AB")
      (libsource (lib "eagle-import") (part "DIODE-DO219AB"))
    )
    (comp (ref "IC7")
      (value "NE5534D")
      (footprint "eagle-import:SO08")
      (libsource (lib "eagle-import") (part "NE5534D"))
    )
    (comp (ref "IC8")
      (value "TL074D")
      (footprint "eagle-import:SO14")
      (libsource (lib "eagle-import") (part "TL074D"))
    )
    (comp (ref "L1")
      (value "L200R")
      (footprint "eagle-import:R0805")
      (libsource (lib "eagle-import") (part "L-EU_L0805"))
    )
    (comp (ref "L3")
      (value "200R")
      (footprint "eagle-import:R0805")
      (libsource (lib "eagle-import") (part "L-EU_L0805"))
    )
    (comp (ref "R29")
      (value "220k")
      (footprint "eagle-import:R0603")
      (libsource (lib "eagle-import") (part "R-EU_R0603"))
    )
    (comp (ref "R30")
      (value "220k")
      (footprint "eagle-import:R0603")
      (libsource (lib "eagle-import") (part "R-EU_R0603"))
    )
    (comp (ref "R31")
      (value "100k")
      (footprint "eagle-import:R0805")
      (libsource (lib "eagle-import") (part "R-EU_R0805"))
    )
    (comp (ref "R32")
      (value "10k")
      (footprint "eagle-import:R0603")
      (libsource (lib "eagle-import") (part "R-EU_R0603"))
    )
    (comp (ref "R33")
      (value "470")
      (footprint "eagle-import:R0603")
      (libsource (lib "eagle-import") (part "R-EU_R0603"))
    )
    (comp (ref "R36")
      (value "10k")
      (footprint "eagle-import:R0603")
      (libsource (lib "eagle-import") (part "R-EU_R0603"))
    )
    (comp (ref "R37")
      (value "47k")
      (footprint "eagle-import:R0603")
      (libsource (lib "eagle-import") (part "R-EU_R0603"))
    )
    (comp (ref "R38")
      (value "2k2")
      (footprint "eagle-import:R0603")
      (libsource (lib "eagle-import") (part "R-EU_R0603"))
    )
    (comp (ref "R39")
      (value "2k2")
      (footprint "eagle-import:R0603")
      (libsource (lib "eagle-import") (part "R-EU_R0603"))
    )
    (comp (ref "R40")
      (value "1k5")
      (footprint "eagle-import:R1206")
      (libsource (lib "eagle-import") (part "R-EU_R1206"))
    )
    (comp (ref "R41")
      (value "2k2")
      (footprint "eagle-import:R0603")
      (libsource (lib "eagle-import") (part "R-EU_R0603"))
    )
    (comp (ref "R42")
      (value "56k")
      (footprint "eagle-import:R0603")
      (libsource (lib "eagle-import") (part "R-EU_R0603"))
    )
    (comp (ref "R44")
      (value "6k8")
      (footprint "eagle-import:R0603")
      (libsource (lib "eagle-import") (part "R-EU_R0603"))
    )
    (comp (ref "R45")
      (value "43k")
      (footprint "eagle-import:R0603")
      (libsource (lib "eagle-import") (part "R-EU_R0603"))
    )
    (comp (ref "R46")
      (value "10k")
      (footprint "eagle-import:R0603")
      (libsource (lib "eagle-import") (part "R-EU_R0603"))
    )
    (comp (ref "R47")
      (value "68k")
      (footprint "eagle-import:R0603")
      (libsource (lib "eagle-import") (part "R-EU_R0603"))
    )
    (comp (ref "R48")
      (value "20k")
      (footprint "eagle-import:R0603")
      (libsource (lib "eagle-import") (part "R-EU_R0603"))
    )
    (comp (ref "R49")
      (value "47k")
      (footprint "eagle-import:R0603")
      (libsource (lib "eagle-import") (part "R-EU_R0603"))
    )
    (comp (ref "R50")
      (value "47k")
      (footprint "eagle-import:R0603")
      (libsource (lib "eagle-import") (part "R-EU_R0603"))
    )
    (comp (ref "R51")
      (value "1k5")
      (footprint "eagle-import:R0603")
      (libsource (lib "eagle-import") (part "R-EU_R0603"))
    )
    (comp (ref "R52")
      (value "2k2")
      (footprint "eagle-import:R0603")
      (libsource (lib "eagle-import") (part "R-EU_R0603"))
    )
    (comp (ref "R53")
      (value "18k")
      (footprint "eagle-import:R0603")
      (libsource (lib "eagle-import") (part "R-EU_R0603"))
    )
    (comp (ref "R54")
      (value "470")
      (footprint "eagle-import:R0805")
      (libsource (lib "eagle-import") (part "R-EU_R0805"))
    )
    (comp (ref "R82")
      (value "47k")
      (footprint "eagle-import:R0603")
      (libsource (lib "eagle-import") (part "R-EU_R0603"))
    )
    (comp (ref "T2")
      (value "BC847")
      (footprint "eagle-import:SOT23")
      (libsource (lib "eagle-import") (part "BC847"))
    )
    (comp (ref "T3")
      (value "MMBTA92")
      (footprint "eagle-import:SOT23")
      (libsource (lib "eagle-import") (part "MMBTA92"))
    )
    (comp (ref "TP1")
      (value "XA")
      (footprint "eagle-import:B1,27")
      (libsource (lib "eagle-import") (part "TPB1,27"))
    )
    (comp (ref "X2")
      (value "NC3MBH")
      (footprint "eagle-import:NC3MBH")
      (libsource (lib "eagle-import") (part "NC3MBH"))
    )
  )
  (nets
    (net (code "1") (name "+5V") (class "Default")
      (node (ref "C14") (pin "1") (pinfunction "1_1") (pintype "passive"))
      (node (ref "C15") (pin "1") (pinfunction "1_1") (pintype "passive"))
      (node (ref "C30") (pin "1") (pinfunction "1_1") (pintype "passive"))
      (node (ref "C39") (pin "1") (pinfunction "1_1") (pintype "passive"))
      (node (ref "C40") (pin "1") (pinfunction "1_1") (pintype "passive"))
      (node (ref "C69") (pin "1") (pinfunction "1_1") (pintype "passive"))
      (node (ref "C70") (pin "+") (pinfunction "+_+") (pintype "passive"))
      (node (ref "IC11") (pin "2") (pinfunction "VCC_2") (pintype "power_in"))
      (node (ref "IC13") (pin "4") (pinfunction "V+_4") (pintype "power_in"))
      (node (ref "IC2") (pin "4") (pinfunction "V+_4") (pintype "power_in"))
      (node (ref "IC6") (pin "15") (pinfunction "AVCC_15") (pintype "power_in"))
      (node (ref "IC6") (pin "16") (pinfunction "VCC_16") (pintype "power_in"))
      (node (ref "IC6") (pin "5") (pinfunction "A0_5") (pintype "input"))
      (node (ref "IC9") (pin "1") (pinfunction "V+_1") (pintype "power_in"))
      (node (ref "L4") (pin "1") (pinfunction "1_1") (pintype "passive"))
      (node (ref "R77") (pin "2") (pinfunction "2_2") (pintype "passive"))
    )
    (net (code "2") (name "+9V") (class "Default")
      (node (ref "C103") (pin "1") (pinfunction "1_1") (pintype "passive"))
      (node (ref "C104") (pin "1") (pinfunction "1_1") (pintype "passive"))
      (node (ref "C47") (pin "+") (pinfunction "+_+") (pintype "passive"))
      (node (ref "C64") (pin "2") (pinfunction "2_2") (pintype "passive"))
      (node (ref "D101") (pin "C") (pinfunction "K_C") (pintype "bidirectional"))
      (node (ref "D5") (pin "C") (pinfunction "K_C") (pintype "bidirectional"))
      (node (ref "IC4") (pin "9") (pinfunction "V+_9") (pintype "power_in"))
      (node (ref "R103") (pin "2") (pinfunction "2_2") (pintype "passive"))
      (node (ref "R24") (pin "2") (pinfunction "2_2") (pintype "passive"))
    )
    (net (code "3") (name "2V5_A") (class "Default")
      (node (ref "C61") (pin "-") (pinfunction "-_-") (pintype "passive"))
      (node (ref "IC12") (pin "8") (pinfunction "E_8") (pintype "passive"))
      (node (ref "IC13") (pin "13") (pinfunction "-IN_13") (pintype "input"))
      (node (ref "IC13") (pin "14") (pinfunction "OUT_14") (pintype "output"))
      (node (ref "IC2") (pin "10") (pinfunction "+IN_10") (pintype "input"))
      (node (ref "JP1") (pin "22") (pinfunction "22_22") (pintype "passive"))
      (node (ref "R35") (pin "2") (pinfunction "2_2") (pintype "passive"))
      (node (ref "R57") (pin "1") (pinfunction "1_1") (pintype "passive"))
      (node (ref "R59") (pin "2") (pinfunction "2_2") (pintype "passive"))
      (node (ref "R60") (pin "1") (pinfunction "1_1") (pintype "passive"))
    )
    (net (code "4") (name "2V5_D") (class "Default")
      (node (ref "IC3") (pin "13") (pinfunction "-IN_13") (pintype "input"))
      (node (ref "IC3") (pin "14") (pinfunction "OUT_14") (pintype "output"))
      (node (ref "R4") (pin "2") (pinfunction "2_2") (pintype "passive"))
      (node (ref "R6") (pin "1") (pinfunction "1_1") (pintype "passive"))
      (node (ref "R9") (pin "1") (pinfunction "1_1") (pintype "passive"))
    )
    (net (code "5") (name "ABEEP") (class "Default")
      (node (ref "IC1") (pin "43") (pinfunction "(AIN1/OC0)PB3_43") (pintype "bidirectional"))
      (node (ref "R1") (pin "1") (pinfunction "1_1") (pintype "passive"))
    )
    (net (code "6") (name "AGND") (class "Default")
      (node (ref "C32") (pin "2") (pinfunction "2_2") (pintype "passive"))
      (node (ref "IC8") (pin "13") (pinfunction "-IN_13") (pintype "input"))
      (node (ref "IC8") (pin "14") (pinfunction "OUT_14") (pintype "output"))
      (node (ref "R37") (pin "1") (pinfunction "1_1") (pintype "passive"))
      (node (ref "R38") (pin "1") (pinfunction "1_1") (pintype "passive"))
      (node (ref "R44") (pin "2") (pinfunction "2_2") (pintype "passive"))
      (node (ref "R47") (pin "1") (pinfunction "1_1") (pintype "passive"))
      (node (ref "R52") (pin "1") (pinfunction "1_1") (pintype "passive"))
    )
    (net (code "7") (name "AVR_MISO") (class "Default")
      (node (ref "CN1") (pin "16") (pinfunction "16_16") (pintype "bidirectional"))
      (node (ref "IC1") (pin "2") (pinfunction "(MISO)PB6_2") (pintype "bidirectional"))
      (node (ref "SV1") (pin "1") (pinfunction "1_1") (pintype "passive"))
    )
    (net (code "8") (name "AVR_MOSI") (class "Default")
      (node (ref "CN1") (pin "8") (pinfunction "8_8") (pintype "bidirectional"))
      (node (ref "IC1") (pin "1") (pinfunction "(MOSI)PB5_1") (pintype "bidirectional"))
      (node (ref "SV1") (pin "4") (pinfunction "4_4") (pintype "passive"))
    )
    (net (code "9") (name "AVR_RXD") (class "Default")
      (node (ref "IC1") (pin "9") (pinfunction "(RXD)PD0_9") (pintype "bidirectional"))
      (node (ref "JP1") (pin "3") (pinfunction "3_3") (pintype "passive"))
    )
    (net (code "10") (name "AVR_SCK") (class "Default")
      (node (ref "CN1") (pin "9") (pinfunction "9_9") (pintype "bidirectional"))
      (node (ref "IC1") (pin "3") (pinfunction "(SCK)PB7_3") (pintype "bidirectional"))
      (node (ref "SV1") (pin "3") (pinfunction "3_3") (pintype "passive"))
    )
    (net (code "11") (name "AVR_TXD") (class "Default")
      (node (ref "IC1") (pin "10") (pinfunction "(TXD)PD1_10") (pintype "bidirectional"))
      (node (ref "JP1") (pin "1") (pinfunction "1_1") (pintype "passive"))
    )
    (net (code "12") (name "BEEP-18") (class "Default")
      (node (ref "IC1") (pin "41") (pinfunction "(T1)PB1_41") (pintype "bidirectional"))
      (node (ref "IC5") (pin "1") (pinfunction "CTL_1") (pintype "input"))
    )
    (net (code "13") (name "BEEP_A") (class "Default")
      (node (ref "IC5") (pin "4") (pinfunction "NC_4") (pintype "passive"))
      (node (ref "R2") (pin "2") (pinfunction "2_2") (pintype "passive"))
      (node (ref "R5") (pin "2") (pinfunction "2_2") (pintype "passive"))
      (node (ref "T4") (pin "2") (pinfunction "E_2") (pintype "passive"))
    )
    (net (code "14") (name "BEEP_AUDIO") (class "Default")
      (node (ref "C29") (pin "1") (pinfunction "1_1") (pintype "passive"))
      (node (ref "IC3") (pin "1") (pinfunction "OUT_1") (pintype "output"))
      (node (ref "R11") (pin "2") (pinfunction "2_2") (pintype "passive"))
    )
    (net (code "15") (name "BEEP_DRV") (class "Default")
      (node (ref "IC1") (pin "14") (pinfunction "(OC1A)PD5_14") (pintype "bidirectional"))
    )
    (net (code "16") (name "CALL_DRV") (class "Default")
      (node (ref "IC1") (pin "37") (pinfunction "(ADC0)PA0_37") (pintype "bidirectional"))
      (node (ref "R46") (pin "1") (pinfunction "1_1") (pintype "passive"))
    )
    (net (code "17") (name "ENC_A") (class "Default")
      (node (ref "CN1") (pin "3") (pinfunction "3_3") (pintype "bidirectional"))
      (node (ref "IC1") (pin "26") (pinfunction "(TOSC2)PC7_26") (pintype "bidirectional"))
    )
    (net (code "18") (name "ENC_B") (class "Default")
      (node (ref "CN1") (pin "2") (pinfunction "2_2") (pintype "bidirectional"))
      (node (ref "IC1") (pin "25") (pinfunction "(TOSC1)PC6_25") (pintype "bidirectional"))
    )
    (net (code "19") (name "ENC_BTN") (class "Default")
      (node (ref "D8") (pin "A") (pinfunction "A_A") (pintype "bidirectional"))
      (node (ref "IC1") (pin "24") (pinfunction "(TDI)PC5_24") (pintype "bidirectional"))
    )
    (net (code "20") (name "ENC_C") (class "Default")
      (node (ref "CN1") (pin "1") (pinfunction "1_1") (pintype "bidirectional"))
      (node (ref "D7") (pin "C") (pinfunction "K_C") (pintype "bidirectional"))
      (node (ref "D8") (pin "C") (pinfunction "K_C") (pintype "bidirectional"))
    )
    (net (code "21") (name "EXT_AUDIO_L") (class "Default")
      (node (ref "JP1") (pin "21") (pinfunction "21_21") (pintype "passive"))
      (node (ref "R65") (pin "1") (pinfunction "1_1") (pintype "passive"))
    )
    (net (code "22") (name "EXT_AUDIO_R") (class "Default")
      (node (ref "JP1") (pin "20") (pinfunction "20_20") (pintype "passive"))
      (node (ref "R66") (pin "1") (pinfunction "1_1") (pintype "passive"))
    )
    (net (code "23") (name "GND") (class "Default")
      (node (ref "C1") (pin "2") (pinfunction "2_2") (pintype "passive"))
      (node (ref "C10") (pin "2") (pinfunction "2_2") (pintype "passive"))
      (node (ref "C101") (pin "-") (pinfunction "-_-") (pintype "passive"))
      (node (ref "C102") (pin "2") (pinfunction "2_2") (pintype "passive"))
      (node (ref "C104") (pin "2") (pinfunction "2_2") (pintype "passive"))
      (node (ref "C11") (pin "2") (pinfunction "2_2") (pintype "passive"))
      (node (ref "C12") (pin "2") (pinfunction "2_2") (pintype "passive"))
      (node (ref "C13") (pin "2") (pinfunction "2_2") (pintype "passive"))
      (node (ref "C14") (pin "2") (pinfunction "2_2") (pintype "passive"))
      (node (ref "C15") (pin "2") (pinfunction "2_2") (pintype "passive"))
      (node (ref "C16") (pin "1") (pinfunction "1_1") (pintype "passive"))
      (node (ref "C18") (pin "2") (pinfunction "2_2") (pintype "passive"))
      (node (ref "C19") (pin "2") (pinfunction "2_2") (pintype "passive"))
      (node (ref "C2") (pin "2") (pinfunction "2_2") (pintype "passive"))
      (node (ref "C20") (pin "-") (pinfunction "-_-") (pintype "passive"))
      (node (ref "C21") (pin "2") (pinfunction "2_2") (pintype "passive"))
      (node (ref "C25") (pin "2") (pinfunction "2_2") (pintype "passive"))
      (node (ref "C27") (pin "2") (pinfunction "2_2") (pintype "passive"))
      (node (ref "C28") (pin "1") (pinfunction "1_1") (pintype "passive"))
      (node (ref "C3") (pin "2") (pinfunction "2_2") (pintype "passive"))
      (node (ref "C30") (pin "2") (pinfunction "2_2") (pintype "passive"))
      (node (ref "C31") (pin "2") (pinfunction "2_2") (pintype "passive"))
      (node (ref "C33") (pin "2") (pinfunction "2_2") (pintype "passive"))
      (node (ref "C36") (pin "-") (pinfunction "-_-") (pintype "passive"))
      (node (ref "C37") (pin "-") (pinfunction "-_-") (pintype "passive"))
      (node (ref "C38") (pin "2") (pinfunction "2_2") (pintype "passive"))
      (node (ref "C39") (pin "2") (pinfunction "2_2") (pintype "passive"))
      (node (ref "C4") (pin "2") (pinfunction "2_2") (pintype "passive"))
      (node (ref "C40") (pin "2") (pinfunction "2_2") (pintype "passive"))
      (node (ref "C42") (pin "2") (pinfunction "2_2") (pintype "passive"))
      (node (ref "C43") (pin "2") (pinfunction "2_2") (pintype "passive"))
      (node (ref "C44") (pin "-") (pinfunction "-_-") (pintype "passive"))
      (node (ref "C45") (pin "-") (pinfunction "-_-") (pintype "passive"))
      (node (ref "C46") (pin "2") (pinfunction "2_2") (pintype "passive"))
      (node (ref "C47") (pin "-") (pinfunction "-_-") (pintype "passive"))
      (node (ref "C49") (pin "-") (pinfunction "-_-") (pintype "passive"))
      (node (ref "C5") (pin "2") (pinfunction "2_2") (pintype "passive"))
      (node (ref "C50") (pin "-") (pinfunction "-_-") (pintype "passive"))
      (node (ref "C51") (pin "2") (pinfunction "2_2") (pintype "passive"))
      (node (ref "C52") (pin "2") (pinfunction "2_2") (pintype "passive"))
      (node (ref "C53") (pin "-") (pinfunction "-_-") (pintype "passive"))
      (node (ref "C59") (pin "-") (pinfunction "-_-") (pintype "passive"))
      (node (ref "C6") (pin "2") (pinfunction "2_2") (pintype "passive"))
      (node (ref "C62") (pin "-") (pinfunction "-_-") (pintype "passive"))
      (node (ref "C63") (pin "1") (pinfunction "1_1") (pintype "passive"))
      (node (ref "C64") (pin "1") (pinfunction "1_1") (pintype "passive"))
      (node (ref "C65") (pin "2") (pinfunction "2_2") (pintype "passive"))
      (node (ref "C66") (pin "-") (pinfunction "-_-") (pintype "passive"))
      (node (ref "C67") (pin "2") (pinfunction "2_2") (pintype "passive"))
      (node (ref "C68") (pin "2") (pinfunction "2_2") (pintype "passive"))
      (node (ref "C69") (pin "2") (pinfunction "2_2") (pintype "passive"))
      (node (ref "C7") (pin "2") (pinfunction "2_2") (pintype "passive"))
      (node (ref "C70") (pin "-") (pinfunction "-_-") (pintype "passive"))
      (node (ref "C8") (pin "2") (pinfunction "2_2") (pintype "passive"))
      (node (ref "C9") (pin "2") (pinfunction "2_2") (pintype "passive"))
      (node (ref "CN1") (pin "4") (pinfunction "4_4") (pintype "bidirectional"))
      (node (ref "CN1") (pin "7") (pinfunction "7_7") (pintype "bidirectional"))
      (node (ref "D4") (pin "A") (pinfunction "A_A") (pintype "passive"))
      (node (ref "D6") (pin "A") (pinfunction "A_A") (pintype "bidirectional"))
      (node (ref "IC1") (pin "18") (pinfunction "GND1_18") (pintype "power_in"))
      (node (ref "IC1") (pin "28") (pinfunction "GND_28") (pintype "power_in"))
      (node (ref "IC1") (pin "39") (pinfunction "GND2_39") (pintype "power_in"))
      (node (ref "IC1") (pin "6") (pinfunction "GND_6") (pintype "power_in"))
      (node (ref "IC10") (pin "3") (pinfunction "GND_3") (pintype "power_in"))
      (node (ref "IC101") (pin "2") (pinfunction "GND_2") (pintype "power_in"))
      (node (ref "IC11") (pin "3") (pinfunction "GND_3") (pintype "power_in"))
      (node (ref "IC12") (pin "2") (pinfunction "GND_2") (pintype "power_in"))
      (node (ref "IC12") (pin "3") (pinfunction "ADDR_3") (pintype "input"))
      (node (ref "IC12") (pin "TP") (pinfunction "EP_TP") (pintype "passive"))
      (node (ref "IC13") (pin "11") (pinfunction "V-_11") (pintype "power_in"))
      (node (ref "IC15") (pin "3") (pinfunction "GND_3") (pintype "power_in"))
      (node (ref "IC16") (pin "4") (pinfunction "GND_4") (pintype "bidirectional"))
      (node (ref "IC16") (pin "5") (pinfunction "SHDN_5") (pintype "bidirectional"))
      (node (ref "IC17") (pin "4") (pinfunction "V-_4") (pintype "power_in"))
      (node (ref "IC2") (pin "11") (pinfunction "V-_11") (pintype "power_in"))
      (node (ref "IC3") (pin "10") (pinfunction "+IN_10") (pintype "input"))
      (node (ref "IC3") (pin "11") (pinfunction "V-_11") (pintype "power_in"))
      (node (ref "IC3001") (pin "2") (pinfunction "NC_2") (pintype "bidirectional"))
      (node (ref "IC3001") (pin "3") (pinfunction "NC_3") (pintype "bidirectional"))
      (node (ref "IC3001") (pin "6") (pinfunction "GND_6") (pintype "bidirectional"))
      (node (ref "IC4") (pin "8") (pinfunction "GND_8") (pintype "power_in"))
      (node (ref "IC5") (pin "3") (pinfunction "GND_3") (pintype "power_in"))
      (node (ref "IC6") (pin "1") (pinfunction "GND_1") (pintype "power_in"))
      (node (ref "IC6") (pin "12") (pinfunction "~{CE}_12") (pintype "input"))
      (node (ref "IC6") (pin "2") (pinfunction "A2_2") (pintype "input"))
      (node (ref "IC6") (pin "3") (pinfunction "A1_3") (pintype "input"))
      (node (ref "IC7") (pin "4") (pinfunction "V-_4") (pintype "power_in"))
      (node (ref "IC8") (pin "11") (pinfunction "V-_11") (pintype "power_in"))
      (node (ref "IC9") (pin "10") (pinfunction "GND_10") (pintype "power_in"))
      (node (ref "IC9") (pin "7") (pinfunction "SW_7") (pintype "input"))
      (node (ref "JP1") (pin "10") (pinfunction "10_10") (pintype "passive"))
      (node (ref "JP1") (pin "19") (pinfunction "19_19") (pintype "passive"))
      (node (ref "JP1") (pin "7") (pinfunction "7_7") (pintype "passive"))
      (node (ref "Q1") (pin "2") (pinfunction "G1_2") (pintype "passive"))
      (node (ref "Q1") (pin "4") (pinfunction "G2_4") (pintype "passive"))
      (node (ref "R102") (pin "1") (pinfunction "1_1") (pintype "passive"))
      (node (ref "R13") (pin "1") (pinfunction "1_1") (pintype "passive"))
      (node (ref "R15") (pin "1") (pinfunction "1_1") (pintype "passive"))
      (node (ref "R17") (pin "1") (pinfunction "1_1") (pintype "passive"))
      (node (ref "R2") (pin "1") (pinfunction "1_1") (pintype "passive"))
      (node (ref "R21") (pin "1") (pinfunction "1_1") (pintype "passive"))
      (node (ref "R23") (pin "1") (pinfunction "1_1") (pintype "passive"))
      (node (ref "R28") (pin "1") (pinfunction "1_1") (pintype "passive"))
      (node (ref "R30") (pin "1") (pinfunction "1_1") (pintype "passive"))
      (node (ref "R31") (pin "2") (pinfunction "2_2") (pintype "passive"))
      (node (ref "R56") (pin "1") (pinfunction "1_1") (pintype "passive"))
      (node (ref "R74") (pin "1") (pinfunction "1_1") (pintype "passive"))
      (node (ref "R80") (pin "1") (pinfunction "1_1") (pintype "passive"))
      (node (ref "R81") (pin "1") (pinfunction "1_1") (pintype "passive"))
      (node (ref "SV1") (pin "6") (pinfunction "6_6") (pintype "passive"))
      (node (ref "T2") (pin "2") (pinfunction "E_2") (pintype "passive"))
      (node (ref "X2") (pin "1") (pinfunction "1_1") (pintype "passive"))
      (node (ref "X3") (pin "1") (pinfunction "1_1") (pintype "passive"))
      (node (ref "X3") (pin "3") (pinfunction "3_3") (pintype "passive"))
    )
    (net (code "24") (name "HPA_L") (class "Default")
      (node (ref "IC13") (pin "8") (pinfunction "OUT_8") (pintype "output"))
      (node (ref "IC13") (pin "9") (pinfunction "-IN_9") (pintype "input"))
      (node (ref "R75") (pin "1") (pinfunction "1_1") (pintype "passive"))
    )
    (net (code "25") (name "HPA_R") (class "Default")
      (node (ref "IC13") (pin "6") (pinfunction "-IN_6") (pintype "input"))
      (node (ref "IC13") (pin "7") (pinfunction "OUT_7") (pintype "output"))
      (node (ref "R76") (pin "1") (pinfunction "1_1") (pintype "passive"))
    )
    (net (code "26") (name "LINE") (class "Default")
      (node (ref "C19") (pin "1") (pinfunction "1_1") (pintype "passive"))
      (node (ref "C56") (pin "1") (pinfunction "1_1") (pintype "passive"))
      (node (ref "L1") (pin "1") (pinfunction "1_1") (pintype "passive"))
      (node (ref "R33") (pin "2") (pinfunction "2_2") (pintype "passive"))
      (node (ref "R40") (pin "2") (pinfunction "2_2") (pintype "passive"))
      (node (ref "R82") (pin "1") (pinfunction "1_1") (pintype "passive"))
    )
    (net (code "27") (name "MIC+20") (class "Default")
      (node (ref "IC1") (pin "12") (pinfunction "(INT1)PD3_12") (pintype "bidirectional"))
      (node (ref "IC4") (pin "13") (pinfunction "GAINSW_13") (pintype "input"))
    )
    (net (code "28") (name "MIC-10") (class "Default")
      (node (ref "IC1") (pin "13") (pinfunction "(OC1B)PD4_13") (pintype "bidirectional"))
      (node (ref "IC15") (pin "1") (pinfunction "CTL_1") (pintype "input"))
    )
    (net (code "29") (name "MIC_AUDIO") (class "Default")
      (node (ref "IC10") (pin "4") (pinfunction "NC_4") (pintype "passive"))
      (node (ref "IC15") (pin "5") (pinfunction "COM_5") (pintype "passive"))
      (node (ref "JP1") (pin "17") (pinfunction "17_17") (pintype "passive"))
    )
    (net (code "30") (name "MUTE_MIC") (class "Default")
      (node (ref "IC1") (pin "11") (pinfunction "(INT0)PD2_11") (pintype "bidirectional"))
      (node (ref "IC10") (pin "1") (pinfunction "CTL_1") (pintype "input"))
    )
    (net (code "31") (name "Net-(C16-Pad2)") (class "Default")
      (node (ref "C16") (pin "2") (pinfunction "2_2") (pintype "passive"))
      (node (ref "R31") (pin "1") (pinfunction "1_1") (pintype "passive"))
      (node (ref "X2") (pin "G") (pinfunction "G_G") (pintype "passive"))
    )
    (net (code "32") (name "Net-(C17-Pad+)") (class "Default")
      (node (ref "C17") (pin "+") (pinfunction "+_+") (pintype "passive"))
      (node (ref "R32") (pin "1") (pinfunction "1_1") (pintype "passive"))
    )
    (net (code "33") (name "Net-(C18-Pad1)") (class "Default")
      (node (ref "C18") (pin "1") (pinfunction "1_1") (pintype "passive"))
      (node (ref "L1") (pin "2") (pinfunction "2_2") (pintype "passive"))
      (node (ref "R33") (pin "1") (pinfunction "1_1") (pintype "passive"))
      (node (ref "X2") (pin "3") (pinfunction "3_3") (pintype "passive"))
    )
    (net (code "34") (name "Net-(C28-Pad2)") (class "Default")
      (node (ref "C28") (pin "2") (pinfunction "2_2") (pintype "passive"))
      (node (ref "R41") (pin "2") (pinfunction "2_2") (pintype "passive"))
      (node (ref "R42") (pin "2") (pinfunction "2_2") (pintype "passive"))
    )
    (net (code "35") (name "Net-(C29-Pad2)") (class "Default")
      (node (ref "C29") (pin "2") (pinfunction "2_2") (pintype "passive"))
      (node (ref "R62") (pin "1") (pinfunction "1_1") (pintype "passive"))
    )
    (net (code "36") (name "Net-(C33-Pad1)") (class "Default")
      (node (ref "C33") (pin "1") (pinfunction "1_1") (pintype "passive"))
      (node (ref "R49") (pin "2") (pinfunction "2_2") (pintype "passive"))
      (node (ref "R50") (pin "1") (pinfunction "1_1") (pintype "passive"))
    )
    (net (code "37") (name "Net-(C35-Pad+)") (class "Default")
      (node (ref "C35") (pin "+") (pinfunction "+_+") (pintype "passive"))
      (node (ref "R51") (pin "2") (pinfunction "2_2") (pintype "passive"))
      (node (ref "R52") (pin "2") (pinfunction "2_2") (pintype "passive"))
    )
    (net (code "38") (name "Net-(C42-Pad1)") (class "Default")
      (node (ref "C42") (pin "1") (pinfunction "1_1") (pintype "passive"))
      (node (ref "D2") (pin "C") (pinfunction "C_C") (pintype "passive"))
      (node (ref "L3") (pin "2") (pinfunction "2_2") (pintype "passive"))
    )
    (net (code "39") (name "Net-(C48-Pad1)") (class "Default")
      (node (ref "C48") (pin "1") (pinfunction "1_1") (pintype "passive"))
      (node (ref "R69") (pin "1") (pinfunction "1_1") (pintype "passive"))
      (node (ref "X3") (pin "2") (pinfunction "2_2") (pintype "passive"))
    )
    (net (code "40") (name "Net-(C49-Pad+)") (class "Default")
      (node (ref "C49") (pin "+") (pinfunction "+_+") (pintype "passive"))
      (node (ref "R26") (pin "1") (pinfunction "1_1") (pintype "passive"))
    )
    (net (code "41") (name "Net-(C54-Pad-)") (class "Default")
      (node (ref "C54") (pin "-") (pinfunction "-_-") (pintype "passive"))
      (node (ref "R80") (pin "2") (pinfunction "2_2") (pintype "passive"))
      (node (ref "X3") (pin "5") (pinfunction "5_5") (pintype "passive"))
    )
    (net (code "42") (name "Net-(C55-Pad-)") (class "Default")
      (node (ref "C55") (pin "-") (pinfunction "-_-") (pintype "passive"))
      (node (ref "R81") (pin "2") (pinfunction "2_2") (pintype "passive"))
      (node (ref "X3") (pin "4") (pinfunction "4_4") (pintype "passive"))
    )
    (net (code "43") (name "Net-(C56-Pad2)") (class "Default")
      (node (ref "C56") (pin "2") (pinfunction "2_2") (pintype "passive"))
      (node (ref "C58") (pin "2") (pinfunction "2_2") (pintype "passive"))
      (node (ref "R45") (pin "1") (pinfunction "1_1") (pintype "passive"))
    )
    (net (code "44") (name "Net-(C57-Pad1)") (class "Default")
      (node (ref "C57") (pin "1") (pinfunction "1_1") (pintype "passive"))
      (node (ref "R42") (pin "1") (pinfunction "1_1") (pintype "passive"))
    )
    (net (code "45") (name "Net-(C58-Pad1)") (class "Default")
      (node (ref "C58") (pin "1") (pinfunction "1_1") (pintype "passive"))
      (node (ref "R82") (pin "2") (pinfunction "2_2") (pintype "passive"))
    )
    (net (code "46") (name "Net-(C65-Pad1)") (class "Default")
      (node (ref "C65") (pin "1") (pinfunction "1_1") (pintype "passive"))
      (node (ref "R28") (pin "2") (pinfunction "2_2") (pintype "passive"))
      (node (ref "X3") (pin "G") (pinfunction "G_G") (pintype "passive"))
    )
    (net (code "47") (name "Net-(C66-Pad+)") (class "Default")
      (node (ref "C66") (pin "+") (pinfunction "+_+") (pintype "passive"))
      (node (ref "R69") (pin "2") (pinfunction "2_2") (pintype "passive"))
      (node (ref "R70") (pin "1") (pinfunction "1_1") (pintype "passive"))
    )
    (net (code "48") (name "Net-(D6-K)") (class "Default")
      (node (ref "C48") (pin "2") (pinfunction "2_2") (pintype "passive"))
      (node (ref "D5") (pin "A") (pinfunction "A_A") (pintype "bidirectional"))
      (node (ref "D6") (pin "C") (pinfunction "K_C") (pintype "bidirectional"))
      (node (ref "IC4") (pin "14") (pinfunction "IN_14") (pintype "input"))
    )
    (net (code "49") (name "Net-(IC1-AREF)") (class "Default")
      (node (ref "C6") (pin "1") (pinfunction "1_1") (pintype "passive"))
      (node (ref "IC1") (pin "29") (pinfunction "AREF_29") (pintype "passive"))
    )
    (net (code "50") (name "Net-(IC1-XTAL1)") (class "Default")
      (node (ref "C2") (pin "1") (pinfunction "1_1") (pintype "passive"))
      (node (ref "IC1") (pin "8") (pinfunction "XTAL1_8") (pintype "bidirectional"))
      (node (ref "Q1") (pin "3") (pinfunction "2_3") (pintype "passive"))
    )
    (net (code "51") (name "Net-(IC1-XTAL2)") (class "Default")
      (node (ref "C1") (pin "1") (pinfunction "1_1") (pintype "passive"))
      (node (ref "IC1") (pin "7") (pinfunction "XTAL2_7") (pintype "bidirectional"))
      (node (ref "Q1") (pin "1") (pinfunction "1_1") (pintype "passive"))
    )
    (net (code "52") (name "Net-(IC2A-+IN)") (class "Default")
      (node (ref "IC2") (pin "3") (pinfunction "+IN_3") (pintype "input"))
      (node (ref "R66") (pin "2") (pinfunction "2_2") (pintype "passive"))
      (node (ref "R68") (pin "2") (pinfunction "2_2") (pintype "passive"))
    )
    (net (code "53") (name "Net-(IC2A--IN)") (class "Default")
      (node (ref "IC2") (pin "1") (pinfunction "OUT_1") (pintype "output"))
      (node (ref "IC2") (pin "2") (pinfunction "-IN_2") (pintype "input"))
      (node (ref "IC6") (pin "8") (pinfunction "H_8") (pintype "passive"))
    )
    (net (code "54") (name "Net-(IC2B-+IN)") (class "Default")
      (node (ref "IC2") (pin "5") (pinfunction "+IN_5") (pintype "input"))
      (node (ref "R65") (pin "2") (pinfunction "2_2") (pintype "passive"))
      (node (ref "R67") (pin "2") (pinfunction "2_2") (pintype "passive"))
    )
    (net (code "55") (name "Net-(IC2B--IN)") (class "Default")
      (node (ref "IC2") (pin "6") (pinfunction "-IN_6") (pintype "input"))
      (node (ref "IC2") (pin "7") (pinfunction "OUT_7") (pintype "output"))
      (node (ref "IC6") (pin "10") (pinfunction "H_10") (pintype "passive"))
    )
    (net (code "56") (name "Net-(IC2C--IN)") (class "Default")
      (node (ref "IC2") (pin "9") (pinfunction "-IN_9") (pintype "input"))
      (node (ref "R62") (pin "2") (pinfunction "2_2") (pintype "passive"))
      (node (ref "R63") (pin "2") (pinfunction "2_2") (pintype "passive"))
      (node (ref "R64") (pin "1") (pinfunction "1_1") (pintype "passive"))
    )
    (net (code "57") (name "Net-(IC2C-OUT)") (class "Default")
      (node (ref "IC2") (pin "8") (pinfunction "OUT_8") (pintype "output"))
      (node (ref "R64") (pin "2") (pinfunction "2_2") (pintype "passive"))
      (node (ref "R67") (pin "1") (pinfunction "1_1") (pintype "passive"))
      (node (ref "R68") (pin "1") (pinfunction "1_1") (pintype "passive"))
    )
    (net (code "58") (name "Net-(IC2D-+IN)") (class "Default")
      (node (ref "C41") (pin "2") (pinfunction "2_2") (pintype "passive"))
      (node (ref "IC2") (pin "12") (pinfunction "+IN_12") (pintype "input"))
      (node (ref "R59") (pin "1") (pinfunction "1_1") (pintype "passive"))
    )
    (net (code "59") (name "Net-(IC2D--IN)") (class "Default")
      (node (ref "IC2") (pin "13") (pinfunction "-IN_13") (pintype "input"))
      (node (ref "R60") (pin "2") (pinfunction "2_2") (pintype "passive"))
      (node (ref "R61") (pin "1") (pinfunction "1_1") (pintype "passive"))
    )
    (net (code "60") (name "Net-(IC2D-OUT)") (class "Default")
      (node (ref "IC2") (pin "14") (pinfunction "OUT_14") (pintype "output"))
      (node (ref "R61") (pin "2") (pinfunction "2_2") (pintype "passive"))
      (node (ref "R63") (pin "1") (pinfunction "1_1") (pintype "passive"))
    )
    (net (code "61") (name "Net-(IC3A-+IN)") (class "Default")
      (node (ref "IC3") (pin "3") (pinfunction "+IN_3") (pintype "input"))
      (node (ref "R10") (pin "2") (pinfunction "2_2") (pintype "passive"))
      (node (ref "R9") (pin "2") (pinfunction "2_2") (pintype "passive"))
    )
    (net (code "62") (name "Net-(IC3A--IN)") (class "Default")
      (node (ref "IC3") (pin "2") (pinfunction "-IN_2") (pintype "input"))
      (node (ref "R11") (pin "1") (pinfunction "1_1") (pintype "passive"))
    )
    (net (code "63") (name "Net-(IC3B-+IN)") (class "Default")
      (node (ref "IC3") (pin "5") (pinfunction "+IN_5") (pintype "input"))
      (node (ref "R14") (pin "1") (pinfunction "1_1") (pintype "passive"))
      (node (ref "R15") (pin "2") (pinfunction "2_2") (pintype "passive"))
      (node (ref "R18") (pin "1") (pinfunction "1_1") (pintype "passive"))
    )
    (net (code "64") (name "Net-(IC3B--IN)") (class "Default")
      (node (ref "C13") (pin "1") (pinfunction "1_1") (pintype "passive"))
      (node (ref "IC3") (pin "6") (pinfunction "-IN_6") (pintype "input"))
      (node (ref "R16") (pin "1") (pinfunction "1_1") (pintype "passive"))
      (node (ref "R17") (pin "2") (pinfunction "2_2") (pintype "passive"))
    )
    (net (code "65") (name "Net-(IC3C--IN)") (class "Default")
      (node (ref "IC3") (pin "8") (pinfunction "OUT_8") (pintype "output"))
      (node (ref "IC3") (pin "9") (pinfunction "-IN_9") (pintype "input"))
    )
    (net (code "66") (name "Net-(IC3D-+IN)") (class "Default")
      (node (ref "IC3") (pin "12") (pinfunction "+IN_12") (pintype "input"))
      (node (ref "R20") (pin "1") (pinfunction "1_1") (pintype "passive"))
      (node (ref "R21") (pin "2") (pinfunction "2_2") (pintype "passive"))
    )
    (net (code "67") (name "Net-(IC4A-DET)") (class "Default")
      (node (ref "C61") (pin "+") (pinfunction "+_+") (pintype "passive"))
      (node (ref "IC4") (pin "3") (pinfunction "DET_3") (pintype "passive"))
    )
    (net (code "68") (name "Net-(IC4A-G1)") (class "Default")
      (node (ref "IC4") (pin "1") (pinfunction "G1_1") (pintype "passive"))
      (node (ref "R25") (pin "1") (pinfunction "1_1") (pintype "passive"))
      (node (ref "R26") (pin "2") (pinfunction "2_2") (pintype "passive"))
    )
    (net (code "69") (name "Net-(IC4A-G2)") (class "Default")
      (node (ref "IC4") (pin "2") (pinfunction "G2_2") (pintype "passive"))
      (node (ref "R25") (pin "2") (pinfunction "2_2") (pintype "passive"))
    )
    (net (code "70") (name "Net-(IC4A-INT)") (class "Default")
      (node (ref "C59") (pin "+") (pinfunction "+_+") (pintype "passive"))
      (node (ref "IC4") (pin "12") (pinfunction "INT_12") (pintype "passive"))
    )
    (net (code "71") (name "Net-(IC4A-OUT)") (class "Default")
      (node (ref "IC4") (pin "4") (pinfunction "OUT_4") (pintype "output"))
      (node (ref "IC4") (pin "5") (pinfunction "BUFIN_5") (pintype "input"))
    )
    (net (code "72") (name "Net-(IC4A-SENSE)") (class "Default")
      (node (ref "IC4") (pin "11") (pinfunction "SENSE_11") (pintype "passive"))
      (node (ref "R23") (pin "2") (pinfunction "2_2") (pintype "passive"))
    )
    (net (code "73") (name "Net-(IC4B-BUFG)") (class "Default")
      (node (ref "C60") (pin "+") (pinfunction "+_+") (pintype "passive"))
      (node (ref "IC4") (pin "6") (pinfunction "BUFG_6") (pintype "input"))
      (node (ref "IC4") (pin "7") (pinfunction "BUFO_7") (pintype "output"))
    )
    (net (code "74") (name "Net-(IC4B-VREF)") (class "Default")
      (node (ref "C62") (pin "+") (pinfunction "+_+") (pintype "passive"))
      (node (ref "IC4") (pin "10") (pinfunction "VREF_10") (pintype "passive"))
    )
    (net (code "75") (name "Net-(IC5-COM)") (class "Default")
      (node (ref "IC5") (pin "5") (pinfunction "COM_5") (pintype "passive"))
      (node (ref "R10") (pin "1") (pinfunction "1_1") (pintype "passive"))
    )
    (net (code "76") (name "Net-(IC5-NO)") (class "Default")
      (node (ref "IC5") (pin "6") (pinfunction "NO_6") (pintype "passive"))
      (node (ref "R5") (pin "1") (pinfunction "1_1") (pintype "passive"))
      (node (ref "R6") (pin "2") (pinfunction "2_2") (pintype "passive"))
    )
    (net (code "77") (name "Net-(IC6C-SCL)") (class "Default")
      (node (ref "IC6") (pin "14") (pinfunction "SCL_14") (pintype "input"))
      (node (ref "R7") (pin "2") (pinfunction "2_2") (pintype "passive"))
    )
    (net (code "78") (name "Net-(IC6C-SDA)") (class "Default")
      (node (ref "IC6") (pin "13") (pinfunction "SDA_13") (pintype "bidirectional"))
      (node (ref "R8") (pin "2") (pinfunction "2_2") (pintype "passive"))
    )
    (net (code "79") (name "Net-(IC7-+IN)") (class "Default")
      (node (ref "C20") (pin "+") (pinfunction "+_+") (pintype "passive"))
      (node (ref "D1") (pin "A") (pinfunction "A_A") (pintype "passive"))
      (node (ref "IC7") (pin "3") (pinfunction "+IN_3") (pintype "input"))
      (node (ref "IC8") (pin "10") (pinfunction "+IN_10") (pintype "input"))
      (node (ref "IC8") (pin "12") (pinfunction "+IN_12") (pintype "input"))
      (node (ref "R29") (pin "1") (pinfunction "1_1") (pintype "passive"))
      (node (ref "R30") (pin "2") (pinfunction "2_2") (pintype "passive"))
    )
    (net (code "80") (name "Net-(IC7--IN)") (class "Default")
      (node (ref "C22") (pin "2") (pinfunction "2_2") (pintype "passive"))
      (node (ref "IC7") (pin "2") (pinfunction "-IN_2") (pintype "input"))
      (node (ref "R32") (pin "2") (pinfunction "2_2") (pintype "passive"))
      (node (ref "R36") (pin "1") (pinfunction "1_1") (pintype "passive"))
    )
    (net (code "81") (name "Net-(IC7-CMP)") (class "Default")
      (node (ref "C24") (pin "2") (pinfunction "2_2") (pintype "passive"))
      (node (ref "IC7") (pin "5") (pinfunction "CMP_5") (pintype "passive"))
    )
    (net (code "82") (name "Net-(IC7-ON{slash}CMP)") (class "Default")
      (node (ref "C24") (pin "1") (pinfunction "1_1") (pintype "passive"))
      (node (ref "IC7") (pin "8") (pinfunction "ON/CMP_8") (pintype "passive"))
    )
    (net (code "83") (name "Net-(IC7-OUT)") (class "Default")
      (node (ref "C22") (pin "1") (pinfunction "1_1") (pintype "passive"))
      (node (ref "C25") (pin "1") (pinfunction "1_1") (pintype "passive"))
      (node (ref "C26") (pin "1") (pinfunction "1_1") (pintype "passive"))
      (node (ref "IC7") (pin "6") (pinfunction "OUT_6") (pintype "output"))
      (node (ref "R36") (pin "2") (pinfunction "2_2") (pintype "passive"))
    )
    (net (code "84") (name "Net-(IC8A-+IN)") (class "Default")
      (node (ref "C32") (pin "1") (pinfunction "1_1") (pintype "passive"))
      (node (ref "IC8") (pin "3") (pinfunction "+IN_3") (pintype "input"))
      (node (ref "R45") (pin "2") (pinfunction "2_2") (pintype "passive"))
      (node (ref "R47") (pin "2") (pinfunction "2_2") (pintype "passive"))
    )
    (net (code "85") (name "Net-(IC8A--IN)") (class "Default")
      (node (ref "C57") (pin "2") (pinfunction "2_2") (pintype "passive"))
      (node (ref "IC8") (pin "2") (pinfunction "-IN_2") (pintype "input"))
      (node (ref "R44") (pin "1") (pinfunction "1_1") (pintype "passive"))
      (node (ref "R48") (pin "2") (pinfunction "2_2") (pintype "passive"))
    )
    (net (code "86") (name "Net-(IC8A-OUT)") (class "Default")
      (node (ref "IC8") (pin "1") (pinfunction "OUT_1") (pintype "output"))
      (node (ref "R48") (pin "1") (pinfunction "1_1") (pintype "passive"))
      (node (ref "R51") (pin "1") (pinfunction "1_1") (pintype "passive"))
    )
    (net (code "87") (name "Net-(IC8B-+IN)") (class "Default")
      (node (ref "C23") (pin "+") (pinfunction "+_+") (pintype "passive"))
      (node (ref "IC8") (pin "5") (pinfunction "+IN_5") (pintype "input"))
      (node (ref "R37") (pin "2") (pinfunction "2_2") (pintype "passive"))
    )
    (net (code "88") (name "Net-(IC8B--IN)") (class "Default")
      (node (ref "IC8") (pin "6") (pinfunction "-IN_6") (pintype "input"))
      (node (ref "R38") (pin "2") (pinfunction "2_2") (pintype "passive"))
      (node (ref "R39") (pin "1") (pinfunction "1_1") (pintype "passive"))
    )
    (net (code "89") (name "Net-(IC8B-OUT)") (class "Default")
      (node (ref "IC8") (pin "7") (pinfunction "OUT_7") (pintype "output"))
      (node (ref "R39") (pin "2") (pinfunction "2_2") (pintype "passive"))
      (node (ref "R41") (pin "1") (pinfunction "1_1") (pintype "passive"))
    )
    (net (code "90") (name "Net-(IC8C--IN)") (class "Default")
      (node (ref "IC8") (pin "8") (pinfunction "OUT_8") (pintype "output"))
      (node (ref "IC8") (pin "9") (pinfunction "-IN_9") (pintype "input"))
    )
    (net (code "91") (name "Net-(IC9-INT)") (class "Default")
      (node (ref "C36") (pin "+") (pinfunction "+_+") (pintype "passive"))
      (node (ref "IC9") (pin "4") (pinfunction "INT_4") (pintype "bidirectional"))
    )
    (net (code "92") (name "Net-(IC9-SENSE)") (class "Default")
      (node (ref "IC9") (pin "6") (pinfunction "SENSE_6") (pintype "bidirectional"))
      (node (ref "R56") (pin "2") (pinfunction "2_2") (pintype "passive"))
    )
    (net (code "93") (name "Net-(IC9-VREF)") (class "Default")
      (node (ref "C37") (pin "+") (pinfunction "+_+") (pintype "passive"))
      (node (ref "IC9") (pin "5") (pinfunction "VREF_5") (pintype "bidirectional"))
    )
    (net (code "94") (name "Net-(IC10-NO)") (class "Default")
      (node (ref "IC10") (pin "6") (pinfunction "NO_6") (pintype "passive"))
      (node (ref "R57") (pin "2") (pinfunction "2_2") (pintype "passive"))
    )
    (net (code "95") (name "Net-(IC11-NO)") (class "Default")
      (node (ref "C41") (pin "1") (pinfunction "1_1") (pintype "passive"))
      (node (ref "IC11") (pin "6") (pinfunction "NO_6") (pintype "passive"))
    )
    (net (code "96") (name "Net-(IC12A-S)") (class "Default")
      (node (ref "IC12") (pin "7") (pinfunction "S_7") (pintype "passive"))
      (node (ref "IC17") (pin "3") (pinfunction "+IN_3") (pintype "input"))
    )
    (net (code "97") (name "Net-(IC13A-+IN)") (class "Default")
      (node (ref "IC13") (pin "12") (pinfunction "+IN_12") (pintype "input"))
      (node (ref "IC13") (pin "3") (pinfunction "+IN_3") (pintype "input"))
      (node (ref "R74") (pin "2") (pinfunction "2_2") (pintype "passive"))
      (node (ref "R77") (pin "1") (pinfunction "1_1") (pintype "passive"))
    )
    (net (code "98") (name "Net-(IC13A--IN)") (class "Default")
      (node (ref "IC13") (pin "1") (pinfunction "OUT_1") (pintype "output"))
      (node (ref "IC13") (pin "2") (pinfunction "-IN_2") (pintype "input"))
      (node (ref "IC6") (pin "7") (pinfunction "L_7") (pintype "passive"))
      (node (ref "IC6") (pin "9") (pinfunction "L_9") (pintype "passive"))
    )
    (net (code "99") (name "Net-(IC13B-+IN)") (class "Default")
      (node (ref "IC13") (pin "5") (pinfunction "+IN_5") (pintype "input"))
      (node (ref "IC6") (pin "6") (pinfunction "W_6") (pintype "passive"))
    )
    (net (code "100") (name "Net-(IC13C-+IN)") (class "Default")
      (node (ref "IC13") (pin "10") (pinfunction "+IN_10") (pintype "input"))
      (node (ref "IC6") (pin "11") (pinfunction "W_11") (pintype "passive"))
    )
    (net (code "101") (name "Net-(IC15-NC)") (class "Default")
      (node (ref "C60") (pin "-") (pinfunction "-_-") (pintype "passive"))
      (node (ref "IC15") (pin "4") (pinfunction "NC_4") (pintype "passive"))
      (node (ref "R27") (pin "1") (pinfunction "1_1") (pintype "passive"))
    )
    (net (code "102") (name "Net-(IC15-NO)") (class "Default")
      (node (ref "IC15") (pin "6") (pinfunction "NO_6") (pintype "passive"))
      (node (ref "R27") (pin "2") (pinfunction "2_2") (pintype "passive"))
      (node (ref "R35") (pin "1") (pinfunction "1_1") (pintype "passive"))
    )
    (net (code "103") (name "Net-(IC16-BYPASS)") (class "Default")
      (node (ref "C50") (pin "+") (pinfunction "+_+") (pintype "passive"))
      (node (ref "IC16") (pin "3") (pinfunction "BYPASS_3") (pintype "bidirectional"))
    )
    (net (code "104") (name "Net-(IC16-INA)") (class "Default")
      (node (ref "IC16") (pin "2") (pinfunction "INA_2") (pintype "bidirectional"))
      (node (ref "R75") (pin "2") (pinfunction "2_2") (pintype "passive"))
      (node (ref "R78") (pin "1") (pinfunction "1_1") (pintype "passive"))
    )
    (net (code "105") (name "Net-(IC16-INB)") (class "Default")
      (node (ref "IC16") (pin "6") (pinfunction "INB_6") (pintype "bidirectional"))
      (node (ref "R76") (pin "2") (pinfunction "2_2") (pintype "passive"))
      (node (ref "R79") (pin "1") (pinfunction "1_1") (pintype "passive"))
    )
    (net (code "106") (name "Net-(IC16-OUTA)") (class "Default")
      (node (ref "C54") (pin "+") (pinfunction "+_+") (pintype "passive"))
      (node (ref "IC16") (pin "1") (pinfunction "OUTA_1") (pintype "output"))
      (node (ref "R78") (pin "2") (pinfunction "2_2") (pintype "passive"))
    )
    (net (code "107") (name "Net-(IC16-OUTB)") (class "Default")
      (node (ref "C55") (pin "+") (pinfunction "+_+") (pintype "passive"))
      (node (ref "IC16") (pin "7") (pinfunction "OUTB_7") (pintype "output"))
      (node (ref "R79") (pin "2") (pinfunction "2_2") (pintype "passive"))
    )
    (net (code "108") (name "Net-(IC16-V+)") (class "Default")
      (node (ref "C51") (pin "1") (pinfunction "1_1") (pintype "passive"))
      (node (ref "C53") (pin "+") (pinfunction "+_+") (pintype "passive"))
      (node (ref "IC16") (pin "8") (pinfunction "V+_8") (pintype "power_in"))
      (node (ref "L2") (pin "2") (pinfunction "2_2") (pintype "passive"))
    )
    (net (code "109") (name "Net-(IC101-FB)") (class "Default")
      (node (ref "C103") (pin "2") (pinfunction "2_2") (pintype "passive"))
      (node (ref "IC101") (pin "3") (pinfunction "FB_3") (pintype "bidirectional"))
      (node (ref "R102") (pin "2") (pinfunction "2_2") (pintype "passive"))
      (node (ref "R103") (pin "1") (pinfunction "1_1") (pintype "passive"))
    )
    (net (code "110") (name "Net-(IC101-SW)") (class "Default")
      (node (ref "D101") (pin "A") (pinfunction "A_A") (pintype "bidirectional"))
      (node (ref "IC101") (pin "1") (pinfunction "SW_1") (pintype "bidirectional"))
      (node (ref "L101") (pin "P$2") (pinfunction "P$2_P$2") (pintype "passive"))
    )
    (net (code "111") (name "Net-(IC3001-CB)") (class "Default")
      (node (ref "C3007") (pin "1") (pinfunction "1_1") (pintype "passive"))
      (node (ref "IC3001") (pin "1") (pinfunction "CB_1") (pintype "bidirectional"))
    )
    (net (code "112") (name "Net-(IC3001-OUT)") (class "Default")
      (node (ref "C3007") (pin "2") (pinfunction "2_2") (pintype "passive"))
      (node (ref "D4") (pin "C") (pinfunction "C_C") (pintype "passive"))
      (node (ref "IC3001") (pin "8") (pinfunction "OUT_8") (pintype "bidirectional"))
      (node (ref "L3001") (pin "P$1") (pinfunction "P$1_P$1") (pintype "passive"))
    )
    (net (code "113") (name "Net-(T2-B)") (class "Default")
      (node (ref "R46") (pin "2") (pinfunction "2_2") (pintype "passive"))
      (node (ref "T2") (pin "1") (pinfunction "B_1") (pintype "passive"))
    )
    (net (code "114") (name "Net-(T2-C)") (class "Default")
      (node (ref "R49") (pin "1") (pinfunction "1_1") (pintype "passive"))
      (node (ref "T2") (pin "3") (pinfunction "C_3") (pintype "passive"))
    )
    (net (code "115") (name "Net-(T3-B)") (class "Default")
      (node (ref "C34") (pin "2") (pinfunction "2_2") (pintype "passive"))
      (node (ref "R50") (pin "2") (pinfunction "2_2") (pintype "passive"))
      (node (ref "R53") (pin "1") (pinfunction "1_1") (pintype "passive"))
      (node (ref "T3") (pin "1") (pinfunction "B_1") (pintype "passive"))
    )
    (net (code "116") (name "Net-(T3-E)") (class "Default")
      (node (ref "R54") (pin "1") (pinfunction "1_1") (pintype "passive"))
      (node (ref "T3") (pin "2") (pinfunction "E_2") (pintype "passive"))
    )
    (net (code "117") (name "Net-(T4-B)") (class "Default")
      (node (ref "C4") (pin "1") (pinfunction "1_1") (pintype "passive"))
      (node (ref "R1") (pin "2") (pinfunction "2_2") (pintype "passive"))
      (node (ref "R4") (pin "1") (pinfunction "1_1") (pintype "passive"))
      (node (ref "T4") (pin "1") (pinfunction "B_1") (pintype "passive"))
    )
    (net (code "118") (name "Net-(T4-C)") (class "Default")
      (node (ref "C12") (pin "1") (pinfunction "1_1") (pintype "passive"))
      (node (ref "R22") (pin "1") (pinfunction "1_1") (pintype "passive"))
      (node (ref "T4") (pin "3") (pinfunction "C_3") (pintype "passive"))
    )
    (net (code "119") (name "Net-(T5-D)") (class "Default")
      (node (ref "R70") (pin "2") (pinfunction "2_2") (pintype "passive"))
      (node (ref "T5") (pin "3") (pinfunction "D_3") (pintype "passive"))
    )
    (net (code "120") (name "RX_AUDIO") (class "Default")
      (node (ref "C35") (pin "-") (pinfunction "-_-") (pintype "passive"))
      (node (ref "JP1") (pin "12") (pinfunction "12_12") (pintype "passive"))
      (node (ref "R55") (pin "2") (pinfunction "2_2") (pintype "passive"))
    )
    (net (code "121") (name "RX_AUD_FLT") (class "Default")
      (node (ref "IC9") (pin "3") (pinfunction "INA_3") (pintype "passive"))
      (node (ref "IC9") (pin "8") (pinfunction "INB_8") (pintype "passive"))
      (node (ref "JP1") (pin "11") (pinfunction "11_11") (pintype "passive"))
      (node (ref "R19") (pin "1") (pinfunction "1_1") (pintype "passive"))
      (node (ref "R55") (pin "1") (pinfunction "1_1") (pintype "passive"))
    )
    (net (code "122") (name "RX_AUD_LIM") (class "Default")
      (node (ref "IC9") (pin "9") (pinfunction "OUTB_9") (pintype "output"))
      (node (ref "JP1") (pin "14") (pinfunction "14_14") (pintype "passive"))
      (node (ref "R19") (pin "2") (pinfunction "2_2") (pintype "passive"))
      (node (ref "R58") (pin "1") (pinfunction "1_1") (pintype "passive"))
    )
    (net (code "123") (name "RX_AUD_RET") (class "Default")
      (node (ref "IC11") (pin "5") (pinfunction "COM_5") (pintype "passive"))
      (node (ref "JP1") (pin "13") (pinfunction "13_13") (pintype "passive"))
      (node (ref "R58") (pin "2") (pinfunction "2_2") (pintype "passive"))
    )
    (net (code "124") (name "SCL") (class "Default")
      (node (ref "CN1") (pin "5") (pinfunction "5_5") (pintype "bidirectional"))
      (node (ref "IC1") (pin "19") (pinfunction "PC0(SCL)_19") (pintype "bidirectional"))
      (node (ref "IC12") (pin "5") (pinfunction "SCL_5") (pintype "input"))
      (node (ref "JP1") (pin "8") (pinfunction "8_8") (pintype "passive"))
      (node (ref "R7") (pin "1") (pinfunction "1_1") (pintype "passive"))
      (node (ref "R72") (pin "1") (pinfunction "1_1") (pintype "passive"))
    )
    (net (code "125") (name "SDA") (class "Default")
      (node (ref "CN1") (pin "6") (pinfunction "6_6") (pintype "bidirectional"))
      (node (ref "IC1") (pin "20") (pinfunction "PC1(SDA)_20") (pintype "bidirectional"))
      (node (ref "IC12") (pin "4") (pinfunction "SDA_4") (pintype "bidirectional"))
      (node (ref "JP1") (pin "5") (pinfunction "5_5") (pintype "passive"))
      (node (ref "R73") (pin "1") (pinfunction "1_1") (pintype "passive"))
      (node (ref "R8") (pin "1") (pinfunction "1_1") (pintype "passive"))
    )
    (net (code "126") (name "ST_DRIVE") (class "Default")
      (node (ref "IC12") (pin "1") (pinfunction "A_1") (pintype "passive"))
      (node (ref "IC17") (pin "6") (pinfunction "-IN_6") (pintype "input"))
      (node (ref "IC17") (pin "7") (pinfunction "OUT_7") (pintype "output"))
    )
    (net (code "127") (name "ST_IN") (class "Default")
      (node (ref "C23") (pin "-") (pinfunction "-_-") (pintype "passive"))
      (node (ref "IC17") (pin "1") (pinfunction "OUT_1") (pintype "output"))
      (node (ref "IC17") (pin "2") (pinfunction "-IN_2") (pintype "input"))
    )
    (net (code "128") (name "TC_IN") (class "Default")
      (node (ref "IC1") (pin "15") (pinfunction "(ICP)PD6_15") (pintype "bidirectional"))
      (node (ref "JP1") (pin "4") (pinfunction "4_4") (pintype "passive"))
    )
    (net (code "129") (name "TXA") (class "Default")
      (node (ref "C26") (pin "2") (pinfunction "2_2") (pintype "passive"))
      (node (ref "R16") (pin "2") (pinfunction "2_2") (pintype "passive"))
      (node (ref "R40") (pin "1") (pinfunction "1_1") (pintype "passive"))
      (node (ref "T3") (pin "3") (pinfunction "C_3") (pintype "passive"))
      (node (ref "TP1") (pin "TP") (pinfunction "TP_TP") (pintype "input"))
    )
    (net (code "130") (name "TX_AUDIO") (class "Default")
      (node (ref "C17") (pin "-") (pinfunction "-_-") (pintype "passive"))
      (node (ref "IC17") (pin "5") (pinfunction "+IN_5") (pintype "input"))
      (node (ref "JP1") (pin "15") (pinfunction "15_15") (pintype "passive"))
      (node (ref "R43") (pin "2") (pinfunction "2_2") (pintype "passive"))
    )
    (net (code "131") (name "TX_INT") (class "Default")
      (node (ref "IC10") (pin "5") (pinfunction "COM_5") (pintype "passive"))
      (node (ref "JP1") (pin "18") (pinfunction "18_18") (pintype "passive"))
      (node (ref "R43") (pin "1") (pinfunction "1_1") (pintype "passive"))
    )
    (net (code "132") (name "V+") (class "Default")
      (node (ref "C21") (pin "1") (pinfunction "1_1") (pintype "passive"))
      (node (ref "C27") (pin "1") (pinfunction "1_1") (pintype "passive"))
      (node (ref "C31") (pin "1") (pinfunction "1_1") (pintype "passive"))
      (node (ref "C34") (pin "1") (pinfunction "1_1") (pintype "passive"))
      (node (ref "D1") (pin "K") (pinfunction "C_K") (pintype "passive"))
      (node (ref "D9") (pin "A") (pinfunction "A_A") (pintype "passive"))
      (node (ref "IC7") (pin "7") (pinfunction "V+_7") (pintype "power_in"))
      (node (ref "IC8") (pin "4") (pinfunction "V+_4") (pintype "power_in"))
      (node (ref "L3") (pin "1") (pinfunction "1_1") (pintype "passive"))
      (node (ref "R29") (pin "2") (pinfunction "2_2") (pintype "passive"))
      (node (ref "R53") (pin "2") (pinfunction "2_2") (pintype "passive"))
      (node (ref "R54") (pin "2") (pinfunction "2_2") (pintype "passive"))
    )
    (net (code "133") (name "VBUS_SENSE") (class "Default")
      (node (ref "C10") (pin "1") (pinfunction "1_1") (pintype "passive"))
      (node (ref "IC1") (pin "35") (pinfunction "(ADC2)PA2_35") (pintype "bidirectional"))
      (node (ref "R12") (pin "1") (pinfunction "1_1") (pintype "passive"))
      (node (ref "R13") (pin "2") (pinfunction "2_2") (pintype "passive"))
    )
    (net (code "134") (name "VCC") (class "Default")
      (node (ref "C101") (pin "+") (pinfunction "+_+") (pintype "passive"))
      (node (ref "C102") (pin "1") (pinfunction "1_1") (pintype "passive"))
      (node (ref "C11") (pin "1") (pinfunction "1_1") (pintype "passive"))
      (node (ref "C3") (pin "1") (pinfunction "1_1") (pintype "passive"))
      (node (ref "C38") (pin "1") (pinfunction "1_1") (pintype "passive"))
      (node (ref "C43") (pin "1") (pinfunction "1_1") (pintype "passive"))
      (node (ref "C44") (pin "+") (pinfunction "+_+") (pintype "passive"))
      (node (ref "C5") (pin "1") (pinfunction "1_1") (pintype "passive"))
      (node (ref "C52") (pin "1") (pinfunction "1_1") (pintype "passive"))
      (node (ref "C63") (pin "2") (pinfunction "2_2") (pintype "passive"))
      (node (ref "C67") (pin "1") (pinfunction "1_1") (pintype "passive"))
      (node (ref "C68") (pin "1") (pinfunction "1_1") (pintype "passive"))
      (node (ref "C7") (pin "1") (pinfunction "1_1") (pintype "passive"))
      (node (ref "C8") (pin "1") (pinfunction "1_1") (pintype "passive"))
      (node (ref "C9") (pin "1") (pinfunction "1_1") (pintype "passive"))
      (node (ref "CN1") (pin "12") (pinfunction "12_12") (pintype "bidirectional"))
      (node (ref "CN1") (pin "15") (pinfunction "15_15") (pintype "bidirectional"))
      (node (ref "D3") (pin "A") (pinfunction "A_A") (pintype "passive"))
      (node (ref "IC1") (pin "17") (pinfunction "VCC1_17") (pintype "power_in"))
      (node (ref "IC1") (pin "27") (pinfunction "AVCC_27") (pintype "power_in"))
      (node (ref "IC1") (pin "38") (pinfunction "VCC2_38") (pintype "power_in"))
      (node (ref "IC1") (pin "5") (pinfunction "VCC_5") (pintype "power_in"))
      (node (ref "IC10") (pin "2") (pinfunction "VCC_2") (pintype "power_in"))
      (node (ref "IC101") (pin "4") (pinfunction "~{SHDN}_4") (pintype "bidirectional"))
      (node (ref "IC101") (pin "5") (pinfunction "VIN_5") (pintype "power_in"))
      (node (ref "IC12") (pin "6") (pinfunction "VCC_6") (pintype "power_in"))
      (node (ref "IC15") (pin "2") (pinfunction "VCC_2") (pintype "power_in"))
      (node (ref "IC17") (pin "8") (pinfunction "V+_8") (pintype "power_in"))
      (node (ref "IC3") (pin "4") (pinfunction "V+_4") (pintype "power_in"))
      (node (ref "IC3001") (pin "4") (pinfunction "FB_4") (pintype "bidirectional"))
      (node (ref "IC5") (pin "2") (pinfunction "VCC_2") (pintype "power_in"))
      (node (ref "JP1") (pin "16") (pinfunction "16_16") (pintype "passive"))
      (node (ref "JP1") (pin "9") (pinfunction "9_9") (pintype "passive"))
      (node (ref "L101") (pin "P$1") (pinfunction "P$1_P$1") (pintype "passive"))
      (node (ref "L2") (pin "1") (pinfunction "1_1") (pintype "passive"))
      (node (ref "L3001") (pin "P$2") (pinfunction "P$2_P$2") (pintype "passive"))
      (node (ref "L4") (pin "2") (pinfunction "2_2") (pintype "passive"))
      (node (ref "R14") (pin "2") (pinfunction "2_2") (pintype "passive"))
      (node (ref "R20") (pin "2") (pinfunction "2_2") (pintype "passive"))
      (node (ref "R22") (pin "2") (pinfunction "2_2") (pintype "passive"))
      (node (ref "R24") (pin "1") (pinfunction "1_1") (pintype "passive"))
      (node (ref "R3") (pin "1") (pinfunction "1_1") (pintype "passive"))
      (node (ref "R71") (pin "2") (pinfunction "2_2") (pintype "passive"))
      (node (ref "R72") (pin "2") (pinfunction "2_2") (pintype "passive"))
      (node (ref "R73") (pin "2") (pinfunction "2_2") (pintype "passive"))
      (node (ref "SV1") (pin "2") (pinfunction "2_2") (pintype "passive"))
      (node (ref "T5") (pin "2") (pinfunction "S_2") (pintype "passive"))
    )
    (net (code "135") (name "V_BUS") (class "Default")
      (node (ref "D2") (pin "A") (pinfunction "A_A") (pintype "passive"))
      (node (ref "X2") (pin "2") (pinfunction "2_2") (pintype "passive"))
    )
    (net (code "136") (name "V_I+") (class "Default")
      (node (ref "C45") (pin "+") (pinfunction "+_+") (pintype "passive"))
      (node (ref "C46") (pin "1") (pinfunction "1_1") (pintype "passive"))
      (node (ref "D3") (pin "C") (pinfunction "C_C") (pintype "passive"))
      (node (ref "D9") (pin "C") (pinfunction "C_C") (pintype "passive"))
      (node (ref "IC3001") (pin "7") (pinfunction "IN_7") (pintype "bidirectional"))
      (node (ref "R12") (pin "2") (pinfunction "2_2") (pintype "passive"))
    )
    (net (code "137") (name "unconnected-(CN1-Pad13)") (class "Default")
      (node (ref "CN1") (pin "13") (pinfunction "13_13") (pintype "bidirectional"))
    )
    (net (code "138") (name "unconnected-(IC1-(ADC1)PA1-Pad36)") (class "Default")
      (node (ref "IC1") (pin "36") (pinfunction "(ADC1)PA1_36") (pintype "bidirectional"))
    )
    (net (code "139") (name "unconnected-(IC1-(ADC4)PA4-Pad33)") (class "Default")
      (node (ref "IC1") (pin "33") (pinfunction "(ADC4)PA4_33") (pintype "bidirectional"))
    )
    (net (code "140") (name "unconnected-(IC1-(ADC5)PA5-Pad32)") (class "Default")
      (node (ref "IC1") (pin "32") (pinfunction "(ADC5)PA5_32") (pintype "bidirectional"))
    )
    (net (code "141") (name "unconnected-(IC1-(ADC6)PA6-Pad31)") (class "Default")
      (node (ref "IC1") (pin "31") (pinfunction "(ADC6)PA6_31") (pintype "bidirectional"))
    )
    (net (code "142") (name "unconnected-(IC1-(ADC7)PA7-Pad30)") (class "Default")
      (node (ref "IC1") (pin "30") (pinfunction "(ADC7)PA7_30") (pintype "bidirectional"))
    )
    (net (code "143") (name "unconnected-(IC1-(OC2)PD7-Pad16)") (class "Default")
      (node (ref "IC1") (pin "16") (pinfunction "(OC2)PD7_16") (pintype "bidirectional"))
    )
    (net (code "144") (name "unconnected-(IC1-(TCK)PC2-Pad21)") (class "Default")
      (node (ref "IC1") (pin "21") (pinfunction "(TCK)PC2_21") (pintype "bidirectional"))
    )
    (net (code "145") (name "unconnected-(IC1-(TDO)PC4-Pad23)") (class "Default")
      (node (ref "IC1") (pin "23") (pinfunction "(TDO)PC4_23") (pintype "bidirectional"))
    )
    (net (code "146") (name "unconnected-(IC7-ON-Pad1)") (class "Default")
      (node (ref "IC7") (pin "1") (pinfunction "ON_1") (pintype "passive"))
    )
    (net (code "147") (name "unconnected-(IC9-OUTA-Pad2)") (class "Default")
      (node (ref "IC9") (pin "2") (pinfunction "OUTA_2") (pintype "output"))
    )
    (net (code "148") (name "unconnected-(IC11-NC-Pad4)") (class "Default")
      (node (ref "IC11") (pin "4") (pinfunction "NC_4") (pintype "passive"))
    )
    (net (code "149") (name "unconnected-(IC3001-EN-Pad5)") (class "Default")
      (node (ref "IC3001") (pin "5") (pinfunction "EN_5") (pintype "bidirectional"))
    )
    (net (code "150") (name "unconnected-(JP1-Pad6)") (class "Default")
      (node (ref "JP1") (pin "6") (pinfunction "6_6") (pintype "passive"))
    )
    (net (code "151") (name "~{AVR_CS0}") (class "Default")
      (node (ref "CN1") (pin "11") (pinfunction "11_11") (pintype "bidirectional"))
      (node (ref "IC1") (pin "44") (pinfunction "(SS)PB4_44") (pintype "bidirectional"))
    )
    (net (code "152") (name "~{AVR_RST}") (class "Default")
      (node (ref "CN1") (pin "14") (pinfunction "14_14") (pintype "bidirectional"))
      (node (ref "IC1") (pin "4") (pinfunction "RESET_4") (pintype "input"))
      (node (ref "R3") (pin "2") (pinfunction "2_2") (pintype "passive"))
      (node (ref "SV1") (pin "5") (pinfunction "5_5") (pintype "passive"))
    )
    (net (code "153") (name "~{CALL_IN}") (class "Default")
      (node (ref "IC1") (pin "40") (pinfunction "(T0/XCK)PB0_40") (pintype "bidirectional"))
      (node (ref "IC3") (pin "7") (pinfunction "OUT_7") (pintype "output"))
      (node (ref "R18") (pin "2") (pinfunction "2_2") (pintype "passive"))
    )
    (net (code "154") (name "~{DRST}") (class "Default")
      (node (ref "CN1") (pin "10") (pinfunction "10_10") (pintype "bidirectional"))
      (node (ref "IC1") (pin "34") (pinfunction "(ADC3)PA3_34") (pintype "bidirectional"))
    )
    (net (code "155") (name "~{MUTE_LINE}") (class "Default")
      (node (ref "IC1") (pin "42") (pinfunction "(AIN0/INT2)PB2_42") (pintype "bidirectional"))
      (node (ref "IC11") (pin "1") (pinfunction "CTL_1") (pintype "input"))
    )
    (net (code "156") (name "~{PHANTOM_ON}") (class "Default")
      (node (ref "IC1") (pin "22") (pinfunction "(TMS)PC3_22") (pintype "bidirectional"))
      (node (ref "R71") (pin "1") (pinfunction "1_1") (pintype "passive"))
      (node (ref "T5") (pin "1") (pinfunction "G_1") (pintype "passive"))
    )
    (net (code "157") (name "~{PON}") (class "Default")
      (node (ref "D7") (pin "A") (pinfunction "A_A") (pintype "bidirectional"))
      (node (ref "JP1") (pin "2") (pinfunction "2_2") (pintype "passive"))
    )
  )
)
